# Ferrofluid_Display.net
KiCad netlist of a schematic drawn in Altium Designer
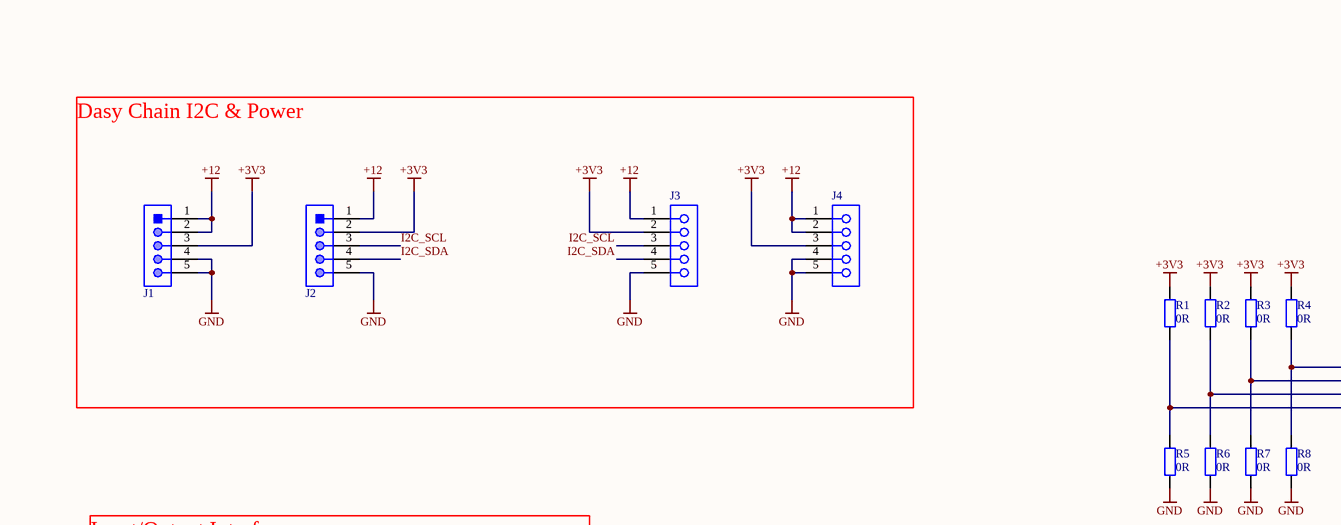
[diagram p0: Ferrofluid_Display.SchDoc, top left]
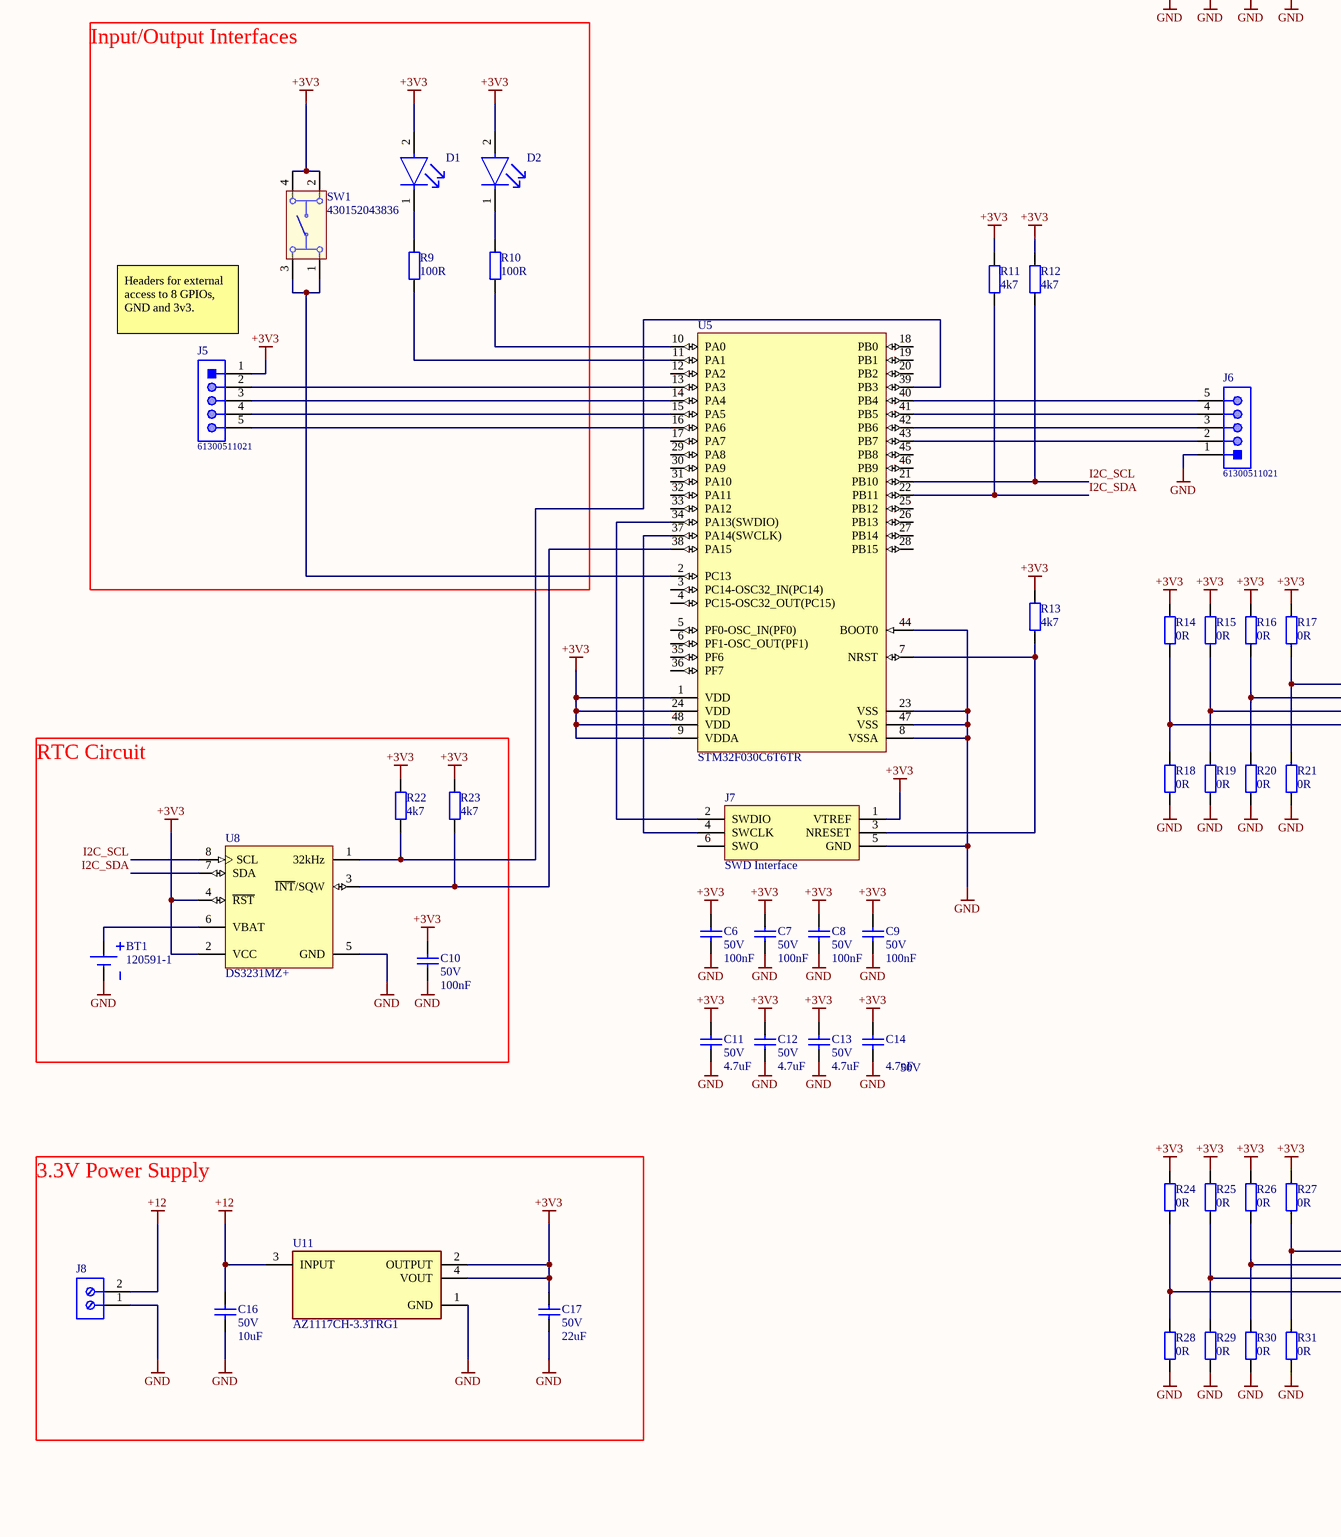
[diagram p1: Ferrofluid_Display.SchDoc, bottom left]
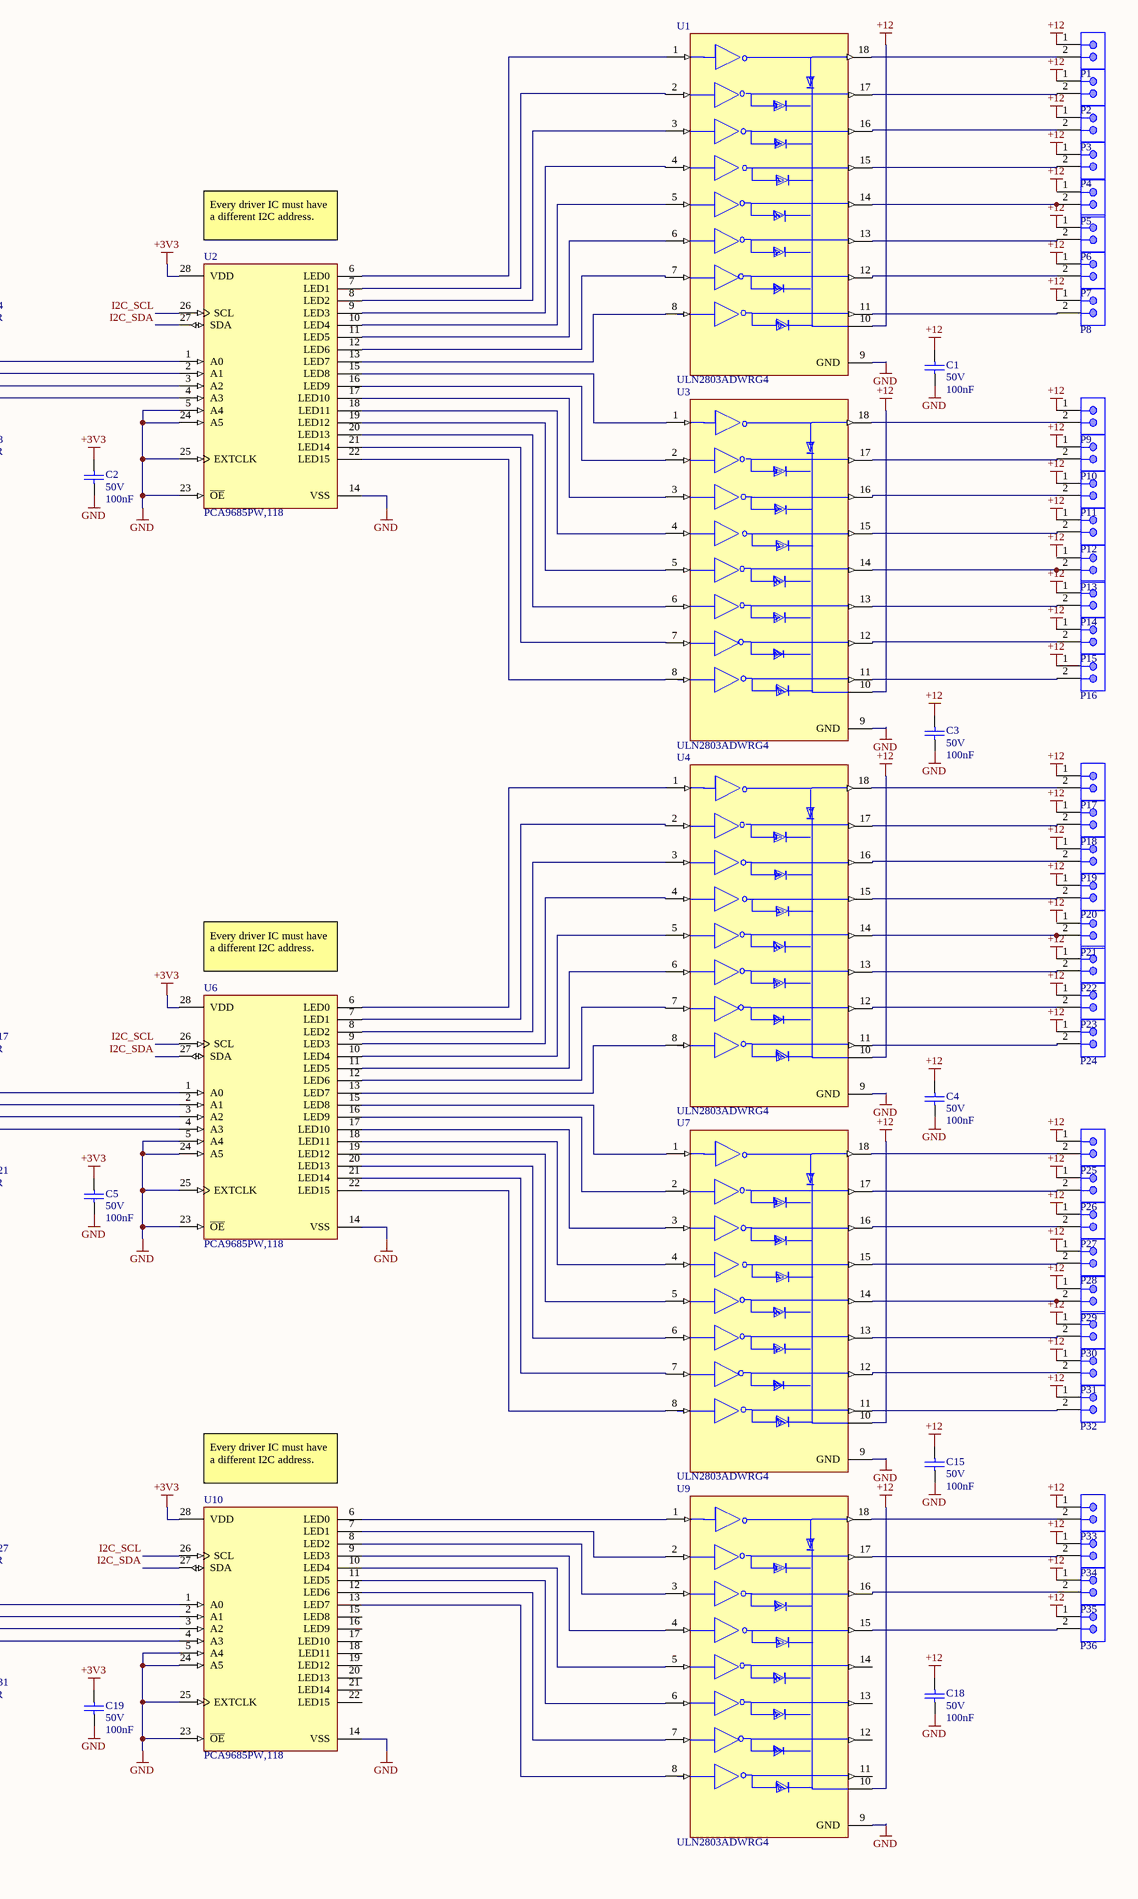
[diagram p2: Ferrofluid_Display.SchDoc, bottom right]

(export (version "E")
  (design (tool "Eeschema 10.0.6"))
  (components
    (comp (ref "BT1")
      (value "120591-1")
      (footprint "TECO-120591-1-2_V")
      (description "Lithium Battery Holder for CR2032 3V Cell")
      (fields (field (name "MANUFACTURER") "TE Connectivity"))
      (libsource (lib "Altium Content Vault") (part "TECO-120591-1-2"))
    )
    (comp (ref "C1")
      (value "100nF")
      (footprint "CAPC2013X88X50ML20T25")
      (description "Ceramic Capacitor X7R")
      (fields (field (name "VOLTAGE RATING") "50V") (field (name "Comment") "Cap_0805"))
      (libsource (lib "Ferrofluid_Display") (part "Cap_0805"))
    )
    (comp (ref "C2")
      (value "100nF")
      (footprint "CAPC2013X88X50ML20T25")
      (description "Ceramic Capacitor X7R")
      (fields (field (name "VOLTAGE RATING") "50V") (field (name "Comment") "Cap_0805"))
      (libsource (lib "Ferrofluid_Display") (part "Cap_0805"))
    )
    (comp (ref "C3")
      (value "100nF")
      (footprint "CAPC2013X88X50ML20T25")
      (description "Ceramic Capacitor X7R")
      (fields (field (name "VOLTAGE RATING") "50V") (field (name "Comment") "Cap_0805"))
      (libsource (lib "Ferrofluid_Display") (part "Cap_0805"))
    )
    (comp (ref "C4")
      (value "100nF")
      (footprint "CAPC2013X88X50ML20T25")
      (description "Ceramic Capacitor X7R")
      (fields (field (name "VOLTAGE RATING") "50V") (field (name "Comment") "Cap_0805"))
      (libsource (lib "Ferrofluid_Display") (part "Cap_0805"))
    )
    (comp (ref "C5")
      (value "100nF")
      (footprint "CAPC2013X88X50ML20T25")
      (description "Ceramic Capacitor X7R")
      (fields (field (name "VOLTAGE RATING") "50V") (field (name "Comment") "Cap_0805"))
      (libsource (lib "Ferrofluid_Display") (part "Cap_0805"))
    )
    (comp (ref "C6")
      (value "100nF")
      (footprint "CAPC2013X88X50ML20T25")
      (description "Ceramic Capacitor X7R")
      (fields (field (name "VOLTAGE RATING") "50V") (field (name "Comment") "Cap_0805"))
      (libsource (lib "Ferrofluid_Display") (part "Cap_0805"))
    )
    (comp (ref "C7")
      (value "100nF")
      (footprint "CAPC2013X88X50ML20T25")
      (description "Ceramic Capacitor X7R")
      (fields (field (name "VOLTAGE RATING") "50V") (field (name "Comment") "Cap_0805"))
      (libsource (lib "Ferrofluid_Display") (part "Cap_0805"))
    )
    (comp (ref "C8")
      (value "100nF")
      (footprint "CAPC2013X88X50ML20T25")
      (description "Ceramic Capacitor X7R")
      (fields (field (name "VOLTAGE RATING") "50V") (field (name "Comment") "Cap_0805"))
      (libsource (lib "Ferrofluid_Display") (part "Cap_0805"))
    )
    (comp (ref "C9")
      (value "100nF")
      (footprint "CAPC2013X88X50ML20T25")
      (description "Ceramic Capacitor X7R")
      (fields (field (name "VOLTAGE RATING") "50V") (field (name "Comment") "Cap_0805"))
      (libsource (lib "Ferrofluid_Display") (part "Cap_0805"))
    )
    (comp (ref "C10")
      (value "100nF")
      (footprint "CAPC2013X88X50ML20T25")
      (description "Ceramic Capacitor X7R")
      (fields (field (name "VOLTAGE RATING") "50V") (field (name "Comment") "Cap_0805"))
      (libsource (lib "Ferrofluid_Display") (part "Cap_0805"))
    )
    (comp (ref "C11")
      (value "4.7uF")
      (footprint "CAPC2013X88X50ML20T25")
      (description "Ceramic Capacitor X7R")
      (fields (field (name "VOLTAGE RATING") "50V") (field (name "Comment") "Cap_0805"))
      (libsource (lib "Ferrofluid_Display") (part "Cap_0805"))
    )
    (comp (ref "C12")
      (value "4.7uF")
      (footprint "CAPC2013X88X50ML20T25")
      (description "Ceramic Capacitor X7R")
      (fields (field (name "VOLTAGE RATING") "50V") (field (name "Comment") "Cap_0805"))
      (libsource (lib "Ferrofluid_Display") (part "Cap_0805"))
    )
    (comp (ref "C13")
      (value "4.7uF")
      (footprint "CAPC2013X88X50ML20T25")
      (description "Ceramic Capacitor X7R")
      (fields (field (name "VOLTAGE RATING") "50V") (field (name "Comment") "Cap_0805"))
      (libsource (lib "Ferrofluid_Display") (part "Cap_0805"))
    )
    (comp (ref "C14")
      (value "4.7uF")
      (footprint "CAPC2013X88X50ML20T25")
      (description "Ceramic Capacitor X7R")
      (fields (field (name "VOLTAGE RATING") "50V") (field (name "Comment") "Cap_0805"))
      (libsource (lib "Ferrofluid_Display") (part "Cap_0805"))
    )
    (comp (ref "C15")
      (value "100nF")
      (footprint "CAPC2013X88X50ML20T25")
      (description "Ceramic Capacitor X7R")
      (fields (field (name "VOLTAGE RATING") "50V") (field (name "Comment") "Cap_0805"))
      (libsource (lib "Ferrofluid_Display") (part "Cap_0805"))
    )
    (comp (ref "C16")
      (value "10uF")
      (footprint "CAPC2013X88X50ML20T25")
      (description "Ceramic Capacitor X7R")
      (fields (field (name "VOLTAGE RATING") "50V") (field (name "Comment") "Cap_0805"))
      (libsource (lib "Ferrofluid_Display") (part "Cap_0805"))
    )
    (comp (ref "C17")
      (value "22uF")
      (footprint "CAPC2013X88X50ML20T25")
      (description "Ceramic Capacitor X7R")
      (fields (field (name "VOLTAGE RATING") "50V") (field (name "Comment") "Cap_0805"))
      (libsource (lib "Ferrofluid_Display") (part "Cap_0805"))
    )
    (comp (ref "C18")
      (value "100nF")
      (footprint "CAPC2013X88X50ML20T25")
      (description "Ceramic Capacitor X7R")
      (fields (field (name "VOLTAGE RATING") "50V") (field (name "Comment") "Cap_0805"))
      (libsource (lib "Ferrofluid_Display") (part "Cap_0805"))
    )
    (comp (ref "C19")
      (value "100nF")
      (footprint "CAPC2013X88X50ML20T25")
      (description "Ceramic Capacitor X7R")
      (fields (field (name "VOLTAGE RATING") "50V") (field (name "Comment") "Cap_0805"))
      (libsource (lib "Ferrofluid_Display") (part "Cap_0805"))
    )
    (comp (ref "D1")
      (value "LTST-C150AKT")
      (footprint "FP-LTST-C150AKT-MFG")
      (description "LED AMBER CLEAR SMD")
      (fields
        (field (name "MANUFACTURER") "Lite-On")
        (field (name "OCTOPART") "https://octopart.com/ltst-c150akt-lite-on-549804")
      )
      (libsource (lib "Altium Content Vault") (part "8706943c75ba83719d021d2fdc84c58"))
    )
    (comp (ref "D2")
      (value "LTST-C150AKT")
      (footprint "FP-LTST-C150AKT-MFG")
      (description "LED AMBER CLEAR SMD")
      (fields
        (field (name "MANUFACTURER") "Lite-On")
        (field (name "OCTOPART") "https://octopart.com/ltst-c150akt-lite-on-549804")
      )
      (libsource (lib "Altium Content Vault") (part "8706943c75ba83719d021d2fdc84c58"))
    )
    (comp (ref "J1")
      (value "61300511021")
      (footprint "61300511021")
      (description "THT Angled Pin Header WR-PHD, Pitch 2.54 mm, Single Row, 5 pins")
      (fields (field (name "MANUFACTURER") "Wurth Elektronik") (field (name "PUBLISHER") "WurthElektronik"))
      (libsource (lib "Altium Content Vault") (part "WE-CN-1P-M-R5"))
    )
    (comp (ref "J2")
      (value "61300511021")
      (footprint "61300511021")
      (description "THT Angled Pin Header WR-PHD, Pitch 2.54 mm, Single Row, 5 pins")
      (fields (field (name "MANUFACTURER") "Wurth Elektronik") (field (name "PUBLISHER") "WurthElektronik"))
      (libsource (lib "Altium Content Vault") (part "WE-CN-1P-M-R5"))
    )
    (comp (ref "J3")
      (value "SSQ-105-02-T-S-RA")
      (footprint "SMTC-SSQ-105-02-X-S-RA")
      (description "SQ Post Socket, Through-hole, Right Angle, -55 to 105 degC, 2.54 mm Pitch, 5-Pin, Female, RoHS")
      (fields (field (name "MANUFACTURER") "Samtec"))
      (libsource (lib "Altium Content Vault") (part "SMTC-SSQ-105-02-X-S-RA"))
    )
    (comp (ref "J4")
      (value "SSQ-105-02-T-S-RA")
      (footprint "SMTC-SSQ-105-02-X-S-RA")
      (description "SQ Post Socket, Through-hole, Right Angle, -55 to 105 degC, 2.54 mm Pitch, 5-Pin, Female, RoHS")
      (fields (field (name "MANUFACTURER") "Samtec"))
      (libsource (lib "Altium Content Vault") (part "SMTC-SSQ-105-02-X-S-RA"))
    )
    (comp (ref "J5")
      (value "61300511021")
      (footprint "61300511021")
      (description "THT Angled Pin Header WR-PHD, Pitch 2.54 mm, Single Row, 5 pins")
      (fields (field (name "MANUFACTURER") "Wurth Elektronik") (field (name "PUBLISHER") "WurthElektronik"))
      (libsource (lib "Altium Content Vault") (part "WE-CN-1P-M-R5"))
    )
    (comp (ref "J6")
      (value "61300511021")
      (footprint "61300511021")
      (description "THT Angled Pin Header WR-PHD, Pitch 2.54 mm, Single Row, 5 pins")
      (fields (field (name "MANUFACTURER") "Wurth Elektronik") (field (name "PUBLISHER") "WurthElektronik"))
      (libsource (lib "") (part "WE-CN-1P-M-R5_1"))
    )
    (comp (ref "J7")
      (value "SWD Interface")
      (footprint "J-Link_6-pin_Needle_Adapter")
      (description "J-Link 6-pin Needle Adapter")
      (libsource (lib "Ferrofluid_Display") (part "J-Link_6-pin_Needle_Adapter"))
    )
    (comp (ref "J8")
      (value "691102710002")
      (footprint "691102710002")
      (description "Series 102 - 5.00 mm Horizontal Entry Modular with Pressure Clamp WR-TBL, 2 pin")
      (fields (field (name "MANUFACTURER") "Wurth Elektronik") (field (name "PUBLISHER") "WurthElektronik"))
      (libsource (lib "Altium Content Vault") (part "WE-CN-1P-F-TB2"))
    )
    (comp (ref "P1")
      (value "5-146280-2")
      (footprint "ELECTROMAGNET")
      (fields (field (name "MANUFACTURER") "TE Connectivity"))
      (libsource (lib "Ferrofluid_Display") (part "Magnet"))
    )
    (comp (ref "P2")
      (value "5-146280-2")
      (footprint "ELECTROMAGNET")
      (fields (field (name "MANUFACTURER") "TE Connectivity"))
      (libsource (lib "Ferrofluid_Display") (part "Magnet"))
    )
    (comp (ref "P3")
      (value "5-146280-2")
      (footprint "ELECTROMAGNET")
      (fields (field (name "MANUFACTURER") "TE Connectivity"))
      (libsource (lib "Ferrofluid_Display") (part "Magnet"))
    )
    (comp (ref "P4")
      (value "5-146280-2")
      (footprint "ELECTROMAGNET")
      (fields (field (name "MANUFACTURER") "TE Connectivity"))
      (libsource (lib "Ferrofluid_Display") (part "Magnet"))
    )
    (comp (ref "P5")
      (value "5-146280-2")
      (footprint "ELECTROMAGNET")
      (fields (field (name "MANUFACTURER") "TE Connectivity"))
      (libsource (lib "Ferrofluid_Display") (part "Magnet"))
    )
    (comp (ref "P6")
      (value "5-146280-2")
      (footprint "ELECTROMAGNET")
      (fields (field (name "MANUFACTURER") "TE Connectivity"))
      (libsource (lib "Ferrofluid_Display") (part "Magnet"))
    )
    (comp (ref "P7")
      (value "5-146280-2")
      (footprint "ELECTROMAGNET")
      (fields (field (name "MANUFACTURER") "TE Connectivity"))
      (libsource (lib "Ferrofluid_Display") (part "Magnet"))
    )
    (comp (ref "P8")
      (value "5-146280-2")
      (footprint "ELECTROMAGNET")
      (fields (field (name "MANUFACTURER") "TE Connectivity"))
      (libsource (lib "Ferrofluid_Display") (part "Magnet"))
    )
    (comp (ref "P9")
      (value "5-146280-2")
      (footprint "ELECTROMAGNET")
      (fields (field (name "MANUFACTURER") "TE Connectivity"))
      (libsource (lib "Ferrofluid_Display") (part "Magnet"))
    )
    (comp (ref "P10")
      (value "5-146280-2")
      (footprint "ELECTROMAGNET")
      (fields (field (name "MANUFACTURER") "TE Connectivity"))
      (libsource (lib "Ferrofluid_Display") (part "Magnet"))
    )
    (comp (ref "P11")
      (value "5-146280-2")
      (footprint "ELECTROMAGNET")
      (fields (field (name "MANUFACTURER") "TE Connectivity"))
      (libsource (lib "Ferrofluid_Display") (part "Magnet"))
    )
    (comp (ref "P12")
      (value "5-146280-2")
      (footprint "ELECTROMAGNET")
      (fields (field (name "MANUFACTURER") "TE Connectivity"))
      (libsource (lib "Ferrofluid_Display") (part "Magnet"))
    )
    (comp (ref "P13")
      (value "5-146280-2")
      (footprint "ELECTROMAGNET")
      (fields (field (name "MANUFACTURER") "TE Connectivity"))
      (libsource (lib "Ferrofluid_Display") (part "Magnet"))
    )
    (comp (ref "P14")
      (value "5-146280-2")
      (footprint "ELECTROMAGNET")
      (fields (field (name "MANUFACTURER") "TE Connectivity"))
      (libsource (lib "Ferrofluid_Display") (part "Magnet"))
    )
    (comp (ref "P15")
      (value "5-146280-2")
      (footprint "ELECTROMAGNET")
      (fields (field (name "MANUFACTURER") "TE Connectivity"))
      (libsource (lib "Ferrofluid_Display") (part "Magnet"))
    )
    (comp (ref "P16")
      (value "5-146280-2")
      (footprint "ELECTROMAGNET")
      (fields (field (name "MANUFACTURER") "TE Connectivity"))
      (libsource (lib "Ferrofluid_Display") (part "Magnet"))
    )
    (comp (ref "P17")
      (value "5-146280-2")
      (footprint "ELECTROMAGNET")
      (fields (field (name "MANUFACTURER") "TE Connectivity"))
      (libsource (lib "Ferrofluid_Display") (part "Magnet"))
    )
    (comp (ref "P18")
      (value "5-146280-2")
      (footprint "ELECTROMAGNET")
      (fields (field (name "MANUFACTURER") "TE Connectivity"))
      (libsource (lib "Ferrofluid_Display") (part "Magnet"))
    )
    (comp (ref "P19")
      (value "5-146280-2")
      (footprint "ELECTROMAGNET")
      (fields (field (name "MANUFACTURER") "TE Connectivity"))
      (libsource (lib "Ferrofluid_Display") (part "Magnet"))
    )
    (comp (ref "P20")
      (value "5-146280-2")
      (footprint "ELECTROMAGNET")
      (fields (field (name "MANUFACTURER") "TE Connectivity"))
      (libsource (lib "Ferrofluid_Display") (part "Magnet"))
    )
    (comp (ref "P21")
      (value "5-146280-2")
      (footprint "ELECTROMAGNET")
      (fields (field (name "MANUFACTURER") "TE Connectivity"))
      (libsource (lib "Ferrofluid_Display") (part "Magnet"))
    )
    (comp (ref "P22")
      (value "5-146280-2")
      (footprint "ELECTROMAGNET")
      (fields (field (name "MANUFACTURER") "TE Connectivity"))
      (libsource (lib "Ferrofluid_Display") (part "Magnet"))
    )
    (comp (ref "P23")
      (value "5-146280-2")
      (footprint "ELECTROMAGNET")
      (fields (field (name "MANUFACTURER") "TE Connectivity"))
      (libsource (lib "Ferrofluid_Display") (part "Magnet"))
    )
    (comp (ref "P24")
      (value "5-146280-2")
      (footprint "ELECTROMAGNET")
      (fields (field (name "MANUFACTURER") "TE Connectivity"))
      (libsource (lib "Ferrofluid_Display") (part "Magnet"))
    )
    (comp (ref "P25")
      (value "5-146280-2")
      (footprint "ELECTROMAGNET")
      (fields (field (name "MANUFACTURER") "TE Connectivity"))
      (libsource (lib "Ferrofluid_Display") (part "Magnet"))
    )
    (comp (ref "P26")
      (value "5-146280-2")
      (footprint "ELECTROMAGNET")
      (fields (field (name "MANUFACTURER") "TE Connectivity"))
      (libsource (lib "Ferrofluid_Display") (part "Magnet"))
    )
    (comp (ref "P27")
      (value "5-146280-2")
      (footprint "ELECTROMAGNET")
      (fields (field (name "MANUFACTURER") "TE Connectivity"))
      (libsource (lib "Ferrofluid_Display") (part "Magnet"))
    )
    (comp (ref "P28")
      (value "5-146280-2")
      (footprint "ELECTROMAGNET")
      (fields (field (name "MANUFACTURER") "TE Connectivity"))
      (libsource (lib "Ferrofluid_Display") (part "Magnet"))
    )
    (comp (ref "P29")
      (value "5-146280-2")
      (footprint "ELECTROMAGNET")
      (fields (field (name "MANUFACTURER") "TE Connectivity"))
      (libsource (lib "Ferrofluid_Display") (part "Magnet"))
    )
    (comp (ref "P30")
      (value "5-146280-2")
      (footprint "ELECTROMAGNET")
      (fields (field (name "MANUFACTURER") "TE Connectivity"))
      (libsource (lib "Ferrofluid_Display") (part "Magnet"))
    )
    (comp (ref "P31")
      (value "5-146280-2")
      (footprint "ELECTROMAGNET")
      (fields (field (name "MANUFACTURER") "TE Connectivity"))
      (libsource (lib "Ferrofluid_Display") (part "Magnet"))
    )
    (comp (ref "P32")
      (value "5-146280-2")
      (footprint "ELECTROMAGNET")
      (fields (field (name "MANUFACTURER") "TE Connectivity"))
      (libsource (lib "Ferrofluid_Display") (part "Magnet"))
    )
    (comp (ref "P33")
      (value "5-146280-2")
      (footprint "ELECTROMAGNET")
      (fields (field (name "MANUFACTURER") "TE Connectivity"))
      (libsource (lib "Ferrofluid_Display") (part "Magnet"))
    )
    (comp (ref "P34")
      (value "5-146280-2")
      (footprint "ELECTROMAGNET")
      (fields (field (name "MANUFACTURER") "TE Connectivity"))
      (libsource (lib "Ferrofluid_Display") (part "Magnet"))
    )
    (comp (ref "P35")
      (value "5-146280-2")
      (footprint "ELECTROMAGNET")
      (fields (field (name "MANUFACTURER") "TE Connectivity"))
      (libsource (lib "Ferrofluid_Display") (part "Magnet"))
    )
    (comp (ref "P36")
      (value "5-146280-2")
      (footprint "ELECTROMAGNET")
      (fields (field (name "MANUFACTURER") "TE Connectivity"))
      (libsource (lib "Ferrofluid_Display") (part "Magnet"))
    )
    (comp (ref "R1")
      (value "0R")
      (footprint "RESC2013X50X30ML20T20")
      (description "Resistor")
      (fields (field (name "TOLERANCE") "1%") (field (name "Comment") "Res_0805"))
      (libsource (lib "Ferrofluid_Display") (part "Res_0805"))
    )
    (comp (ref "R2")
      (value "0R")
      (footprint "RESC2013X50X30ML20T20")
      (description "Resistor")
      (fields (field (name "TOLERANCE") "1%") (field (name "Comment") "Res_0805"))
      (libsource (lib "Ferrofluid_Display") (part "Res_0805"))
    )
    (comp (ref "R3")
      (value "0R")
      (footprint "RESC2013X50X30ML20T20")
      (description "Resistor")
      (fields (field (name "TOLERANCE") "1%") (field (name "Comment") "Res_0805"))
      (libsource (lib "Ferrofluid_Display") (part "Res_0805"))
    )
    (comp (ref "R4")
      (value "0R")
      (footprint "RESC2013X50X30ML20T20")
      (description "Resistor")
      (fields (field (name "TOLERANCE") "1%") (field (name "Comment") "Res_0805"))
      (libsource (lib "Ferrofluid_Display") (part "Res_0805"))
    )
    (comp (ref "R5")
      (value "0R")
      (footprint "RESC2013X50X30ML20T20")
      (description "Resistor")
      (fields (field (name "TOLERANCE") "1%") (field (name "Comment") "Res_0805"))
      (libsource (lib "Ferrofluid_Display") (part "Res_0805"))
    )
    (comp (ref "R6")
      (value "0R")
      (footprint "RESC2013X50X30ML20T20")
      (description "Resistor")
      (fields (field (name "TOLERANCE") "1%") (field (name "Comment") "Res_0805"))
      (libsource (lib "Ferrofluid_Display") (part "Res_0805"))
    )
    (comp (ref "R7")
      (value "0R")
      (footprint "RESC2013X50X30ML20T20")
      (description "Resistor")
      (fields (field (name "TOLERANCE") "1%") (field (name "Comment") "Res_0805"))
      (libsource (lib "Ferrofluid_Display") (part "Res_0805"))
    )
    (comp (ref "R8")
      (value "0R")
      (footprint "RESC2013X50X30ML20T20")
      (description "Resistor")
      (fields (field (name "TOLERANCE") "1%") (field (name "Comment") "Res_0805"))
      (libsource (lib "Ferrofluid_Display") (part "Res_0805"))
    )
    (comp (ref "R9")
      (value "100R")
      (footprint "RESC2013X50X30ML20T20")
      (description "Resistor")
      (fields (field (name "TOLERANCE") "1%") (field (name "Comment") "Res_0805"))
      (libsource (lib "Ferrofluid_Display") (part "Res_0805"))
    )
    (comp (ref "R10")
      (value "100R")
      (footprint "RESC2013X50X30ML20T20")
      (description "Resistor")
      (fields (field (name "TOLERANCE") "1%") (field (name "Comment") "Res_0805"))
      (libsource (lib "Ferrofluid_Display") (part "Res_0805"))
    )
    (comp (ref "R11")
      (value "4k7")
      (footprint "RESC2013X50X30ML20T20")
      (description "Resistor")
      (fields (field (name "TOLERANCE") "1%") (field (name "Comment") "Res_0805"))
      (libsource (lib "Ferrofluid_Display") (part "Res_0805"))
    )
    (comp (ref "R12")
      (value "4k7")
      (footprint "RESC2013X50X30ML20T20")
      (description "Resistor")
      (fields (field (name "TOLERANCE") "1%") (field (name "Comment") "Res_0805"))
      (libsource (lib "Ferrofluid_Display") (part "Res_0805"))
    )
    (comp (ref "R13")
      (value "4k7")
      (footprint "RESC2013X50X30ML20T20")
      (description "Resistor")
      (fields (field (name "TOLERANCE") "1%") (field (name "Comment") "Res_0805"))
      (libsource (lib "Ferrofluid_Display") (part "Res_0805"))
    )
    (comp (ref "R14")
      (value "0R")
      (footprint "RESC2013X50X30ML20T20")
      (description "Resistor")
      (fields (field (name "TOLERANCE") "1%") (field (name "Comment") "Res_0805"))
      (libsource (lib "Ferrofluid_Display") (part "Res_0805"))
    )
    (comp (ref "R15")
      (value "0R")
      (footprint "RESC2013X50X30ML20T20")
      (description "Resistor")
      (fields (field (name "TOLERANCE") "1%") (field (name "Comment") "Res_0805"))
      (libsource (lib "Ferrofluid_Display") (part "Res_0805"))
    )
    (comp (ref "R16")
      (value "0R")
      (footprint "RESC2013X50X30ML20T20")
      (description "Resistor")
      (fields (field (name "TOLERANCE") "1%") (field (name "Comment") "Res_0805"))
      (libsource (lib "Ferrofluid_Display") (part "Res_0805"))
    )
    (comp (ref "R17")
      (value "0R")
      (footprint "RESC2013X50X30ML20T20")
      (description "Resistor")
      (fields (field (name "TOLERANCE") "1%") (field (name "Comment") "Res_0805"))
      (libsource (lib "Ferrofluid_Display") (part "Res_0805"))
    )
    (comp (ref "R18")
      (value "0R")
      (footprint "RESC2013X50X30ML20T20")
      (description "Resistor")
      (fields (field (name "TOLERANCE") "1%") (field (name "Comment") "Res_0805"))
      (libsource (lib "Ferrofluid_Display") (part "Res_0805"))
    )
    (comp (ref "R19")
      (value "0R")
      (footprint "RESC2013X50X30ML20T20")
      (description "Resistor")
      (fields (field (name "TOLERANCE") "1%") (field (name "Comment") "Res_0805"))
      (libsource (lib "Ferrofluid_Display") (part "Res_0805"))
    )
    (comp (ref "R20")
      (value "0R")
      (footprint "RESC2013X50X30ML20T20")
      (description "Resistor")
      (fields (field (name "TOLERANCE") "1%") (field (name "Comment") "Res_0805"))
      (libsource (lib "Ferrofluid_Display") (part "Res_0805"))
    )
    (comp (ref "R21")
      (value "0R")
      (footprint "RESC2013X50X30ML20T20")
      (description "Resistor")
      (fields (field (name "TOLERANCE") "1%") (field (name "Comment") "Res_0805"))
      (libsource (lib "Ferrofluid_Display") (part "Res_0805"))
    )
    (comp (ref "R22")
      (value "4k7")
      (footprint "RESC2013X50X30ML20T20")
      (description "Resistor")
      (fields (field (name "TOLERANCE") "1%") (field (name "Comment") "Res_0805"))
      (libsource (lib "Ferrofluid_Display") (part "Res_0805"))
    )
    (comp (ref "R23")
      (value "4k7")
      (footprint "RESC2013X50X30ML20T20")
      (description "Resistor")
      (fields (field (name "TOLERANCE") "1%") (field (name "Comment") "Res_0805"))
      (libsource (lib "Ferrofluid_Display") (part "Res_0805"))
    )
    (comp (ref "R24")
      (value "0R")
      (footprint "RESC2013X50X30ML20T20")
      (description "Resistor")
      (fields (field (name "TOLERANCE") "1%") (field (name "Comment") "Res_0805"))
      (libsource (lib "Ferrofluid_Display") (part "Res_0805"))
    )
    (comp (ref "R25")
      (value "0R")
      (footprint "RESC2013X50X30ML20T20")
      (description "Resistor")
      (fields (field (name "TOLERANCE") "1%") (field (name "Comment") "Res_0805"))
      (libsource (lib "Ferrofluid_Display") (part "Res_0805"))
    )
    (comp (ref "R26")
      (value "0R")
      (footprint "RESC2013X50X30ML20T20")
      (description "Resistor")
      (fields (field (name "TOLERANCE") "1%") (field (name "Comment") "Res_0805"))
      (libsource (lib "Ferrofluid_Display") (part "Res_0805"))
    )
    (comp (ref "R27")
      (value "0R")
      (footprint "RESC2013X50X30ML20T20")
      (description "Resistor")
      (fields (field (name "TOLERANCE") "1%") (field (name "Comment") "Res_0805"))
      (libsource (lib "Ferrofluid_Display") (part "Res_0805"))
    )
    (comp (ref "R28")
      (value "0R")
      (footprint "RESC2013X50X30ML20T20")
      (description "Resistor")
      (fields (field (name "TOLERANCE") "1%") (field (name "Comment") "Res_0805"))
      (libsource (lib "Ferrofluid_Display") (part "Res_0805"))
    )
    (comp (ref "R29")
      (value "0R")
      (footprint "RESC2013X50X30ML20T20")
      (description "Resistor")
      (fields (field (name "TOLERANCE") "1%") (field (name "Comment") "Res_0805"))
      (libsource (lib "Ferrofluid_Display") (part "Res_0805"))
    )
    (comp (ref "R30")
      (value "0R")
      (footprint "RESC2013X50X30ML20T20")
      (description "Resistor")
      (fields (field (name "TOLERANCE") "1%") (field (name "Comment") "Res_0805"))
      (libsource (lib "Ferrofluid_Display") (part "Res_0805"))
    )
    (comp (ref "R31")
      (value "0R")
      (footprint "RESC2013X50X30ML20T20")
      (description "Resistor")
      (fields (field (name "TOLERANCE") "1%") (field (name "Comment") "Res_0805"))
      (libsource (lib "Ferrofluid_Display") (part "Res_0805"))
    )
    (comp (ref "SW1")
      (value "430152043836")
      (footprint "430152043836")
      (description "WS-TASV SMD Tact Switch 6X6 mm")
      (fields (field (name "MANUFACTURER") "Wuerth Elektronik"))
      (libsource (lib "Altium Content Vault") (part "WE-TACT-SW-4"))
    )
    (comp (ref "U1")
      (value "ULN2803ADWRG4")
      (footprint "FP-DW0018A-MFG")
      (description "TRANS 8NPN DARL 50V 0.5A 18SO")
      (fields
        (field (name "MANUFACTURER") "Texas Instruments")
        (field (name "OCTOPART") "https://octopart.com/uln2803adwrg4-texas+instruments-2343640")
      )
      (libsource (lib "Altium Content Vault") (part "9cac77ed03a2a3c2ed33a396e3d2829"))
    )
    (comp (ref "U2")
      (value "PCA9685PW,118")
      (footprint "FP-SOT361-1-MFG")
      (description "IC LED DRIVER RGBA 28-TSSOP")
      (fields
        (field (name "MANUFACTURER") "NXP Semiconductors")
        (field (name "OCTOPART") "https://octopart.com/pca9685pw%2C118-nxp+semiconductors-11853435")
      )
      (libsource (lib "Altium Content Vault") (part "50b6f6febb80a1ca83d1eae7256368c"))
    )
    (comp (ref "U3")
      (value "ULN2803ADWRG4")
      (footprint "FP-DW0018A-MFG")
      (description "TRANS 8NPN DARL 50V 0.5A 18SO")
      (fields
        (field (name "MANUFACTURER") "Texas Instruments")
        (field (name "OCTOPART") "https://octopart.com/uln2803adwrg4-texas+instruments-2343640")
      )
      (libsource (lib "Altium Content Vault") (part "9cac77ed03a2a3c2ed33a396e3d2829"))
    )
    (comp (ref "U4")
      (value "ULN2803ADWRG4")
      (footprint "FP-DW0018A-MFG")
      (description "TRANS 8NPN DARL 50V 0.5A 18SO")
      (fields
        (field (name "MANUFACTURER") "Texas Instruments")
        (field (name "OCTOPART") "https://octopart.com/uln2803adwrg4-texas+instruments-2343640")
      )
      (libsource (lib "Altium Content Vault") (part "9cac77ed03a2a3c2ed33a396e3d2829"))
    )
    (comp (ref "U5")
      (value "STM32F030C6T6TR")
      (footprint "STM-LQFP48_M")
      (fields (field (name "MANUFACTURER") "STMicroelectronics"))
      (libsource (lib "Altium Content Vault") (part "STM-STM32F030C6-LQFP48_A"))
    )
    (comp (ref "U6")
      (value "PCA9685PW,118")
      (footprint "FP-SOT361-1-MFG")
      (description "IC LED DRIVER RGBA 28-TSSOP")
      (fields
        (field (name "MANUFACTURER") "NXP Semiconductors")
        (field (name "OCTOPART") "https://octopart.com/pca9685pw%2C118-nxp+semiconductors-11853435")
      )
      (libsource (lib "Altium Content Vault") (part "50b6f6febb80a1ca83d1eae7256368c"))
    )
    (comp (ref "U7")
      (value "ULN2803ADWRG4")
      (footprint "FP-DW0018A-MFG")
      (description "TRANS 8NPN DARL 50V 0.5A 18SO")
      (fields
        (field (name "MANUFACTURER") "Texas Instruments")
        (field (name "OCTOPART") "https://octopart.com/uln2803adwrg4-texas+instruments-2343640")
      )
      (libsource (lib "Altium Content Vault") (part "9cac77ed03a2a3c2ed33a396e3d2829"))
    )
    (comp (ref "U8")
      (value "DS3231MZ+")
      (footprint "S8MK+1_N")
      (description "+/-5ppm, MEMS based Real-Time Clock, I2C Interface, 8-Pin SO, -40 to 85 degC, Pb-Free")
      (libsource (lib "Altium Content Vault") (part "PR-RTC-DS3231M-IL8"))
    )
    (comp (ref "U9")
      (value "ULN2803ADWRG4")
      (footprint "FP-DW0018A-MFG")
      (description "TRANS 8NPN DARL 50V 0.5A 18SO")
      (fields
        (field (name "MANUFACTURER") "Texas Instruments")
        (field (name "OCTOPART") "https://octopart.com/uln2803adwrg4-texas+instruments-2343640")
      )
      (libsource (lib "Altium Content Vault") (part "9cac77ed03a2a3c2ed33a396e3d2829"))
    )
    (comp (ref "U10")
      (value "PCA9685PW,118")
      (footprint "FP-SOT361-1-MFG")
      (description "IC LED DRIVER RGBA 28-TSSOP")
      (fields
        (field (name "MANUFACTURER") "NXP Semiconductors")
        (field (name "OCTOPART") "https://octopart.com/pca9685pw%2C118-nxp+semiconductors-11853435")
      )
      (libsource (lib "Altium Content Vault") (part "50b6f6febb80a1ca83d1eae7256368c"))
    )
    (comp (ref "U11")
      (value "AZ1117CH-3.3TRG1")
      (footprint "FP-SOT223-MFG")
      (description "IC REG LINEAR 3.3V 800MA SOT223")
      (libsource (lib "Altium Content Vault") (part "bae10108a039f7d2bfd31a2f0f6c252"))
    )
  )
  (nets
    (net (code "1") (name "+3V3") (class "Default")
      (node (ref "C10") (pin "2") (pinfunction "2_2") (pintype "passive"))
      (node (ref "C11") (pin "2") (pinfunction "2_2") (pintype "passive"))
      (node (ref "C12") (pin "2") (pinfunction "2_2") (pintype "passive"))
      (node (ref "C13") (pin "2") (pinfunction "2_2") (pintype "passive"))
      (node (ref "C14") (pin "2") (pinfunction "2_2") (pintype "passive"))
      (node (ref "C17") (pin "2") (pinfunction "2_2") (pintype "passive"))
      (node (ref "C19") (pin "2") (pinfunction "2_2") (pintype "passive"))
      (node (ref "C2") (pin "2") (pinfunction "2_2") (pintype "passive"))
      (node (ref "C5") (pin "2") (pinfunction "2_2") (pintype "passive"))
      (node (ref "C6") (pin "2") (pinfunction "2_2") (pintype "passive"))
      (node (ref "C7") (pin "2") (pinfunction "2_2") (pintype "passive"))
      (node (ref "C8") (pin "2") (pinfunction "2_2") (pintype "passive"))
      (node (ref "C9") (pin "2") (pinfunction "2_2") (pintype "passive"))
      (node (ref "D1") (pin "2") (pinfunction "A_2") (pintype "passive"))
      (node (ref "D2") (pin "2") (pinfunction "A_2") (pintype "passive"))
      (node (ref "J1") (pin "3") (pinfunction "3_3") (pintype "passive"))
      (node (ref "J2") (pin "2") (pinfunction "2_2") (pintype "passive"))
      (node (ref "J3") (pin "2") (pinfunction "2_2") (pintype "passive"))
      (node (ref "J4") (pin "3") (pinfunction "3_3") (pintype "passive"))
      (node (ref "J5") (pin "1") (pinfunction "1_1") (pintype "passive"))
      (node (ref "J7") (pin "1") (pinfunction "VTREF_1") (pintype "passive"))
      (node (ref "R1") (pin "2") (pinfunction "2_2") (pintype "passive"))
      (node (ref "R11") (pin "2") (pinfunction "2_2") (pintype "passive"))
      (node (ref "R12") (pin "2") (pinfunction "2_2") (pintype "passive"))
      (node (ref "R13") (pin "2") (pinfunction "2_2") (pintype "passive"))
      (node (ref "R14") (pin "2") (pinfunction "2_2") (pintype "passive"))
      (node (ref "R15") (pin "2") (pinfunction "2_2") (pintype "passive"))
      (node (ref "R16") (pin "2") (pinfunction "2_2") (pintype "passive"))
      (node (ref "R17") (pin "2") (pinfunction "2_2") (pintype "passive"))
      (node (ref "R2") (pin "2") (pinfunction "2_2") (pintype "passive"))
      (node (ref "R22") (pin "2") (pinfunction "2_2") (pintype "passive"))
      (node (ref "R23") (pin "2") (pinfunction "2_2") (pintype "passive"))
      (node (ref "R24") (pin "2") (pinfunction "2_2") (pintype "passive"))
      (node (ref "R25") (pin "2") (pinfunction "2_2") (pintype "passive"))
      (node (ref "R26") (pin "2") (pinfunction "2_2") (pintype "passive"))
      (node (ref "R27") (pin "2") (pinfunction "2_2") (pintype "passive"))
      (node (ref "R3") (pin "2") (pinfunction "2_2") (pintype "passive"))
      (node (ref "R4") (pin "2") (pinfunction "2_2") (pintype "passive"))
      (node (ref "SW1") (pin "2") (pinfunction "2_2") (pintype "passive"))
      (node (ref "SW1") (pin "4") (pinfunction "4_4") (pintype "passive"))
      (node (ref "U10") (pin "28") (pinfunction "VDD_28") (pintype "power_in"))
      (node (ref "U11") (pin "2") (pinfunction "OUTPUT_2") (pintype "power_in"))
      (node (ref "U11") (pin "4") (pinfunction "VOUT_4") (pintype "power_in"))
      (node (ref "U2") (pin "28") (pinfunction "VDD_28") (pintype "power_in"))
      (node (ref "U5") (pin "1") (pinfunction "VDD_1") (pintype "power_in"))
      (node (ref "U5") (pin "24") (pinfunction "VDD_24") (pintype "power_in"))
      (node (ref "U5") (pin "48") (pinfunction "VDD_48") (pintype "power_in"))
      (node (ref "U5") (pin "9") (pinfunction "VDDA_9") (pintype "power_in"))
      (node (ref "U6") (pin "28") (pinfunction "VDD_28") (pintype "power_in"))
      (node (ref "U8") (pin "2") (pinfunction "VCC_2") (pintype "power_in"))
      (node (ref "U8") (pin "4") (pinfunction "~{RST}_4") (pintype "bidirectional"))
    )
    (net (code "2") (name "+12") (class "Default")
      (node (ref "C1") (pin "2") (pinfunction "2_2") (pintype "passive"))
      (node (ref "C15") (pin "2") (pinfunction "2_2") (pintype "passive"))
      (node (ref "C16") (pin "2") (pinfunction "2_2") (pintype "passive"))
      (node (ref "C18") (pin "2") (pinfunction "2_2") (pintype "passive"))
      (node (ref "C3") (pin "2") (pinfunction "2_2") (pintype "passive"))
      (node (ref "C4") (pin "2") (pinfunction "2_2") (pintype "passive"))
      (node (ref "J1") (pin "1") (pinfunction "1_1") (pintype "passive"))
      (node (ref "J1") (pin "2") (pinfunction "2_2") (pintype "passive"))
      (node (ref "J2") (pin "1") (pinfunction "1_1") (pintype "passive"))
      (node (ref "J3") (pin "1") (pinfunction "1_1") (pintype "passive"))
      (node (ref "J4") (pin "1") (pinfunction "1_1") (pintype "passive"))
      (node (ref "J4") (pin "2") (pinfunction "2_2") (pintype "passive"))
      (node (ref "J8") (pin "2") (pinfunction "2_2") (pintype "passive"))
      (node (ref "P1") (pin "1") (pinfunction "1_1") (pintype "passive"))
      (node (ref "P10") (pin "1") (pinfunction "1_1") (pintype "passive"))
      (node (ref "P11") (pin "1") (pinfunction "1_1") (pintype "passive"))
      (node (ref "P12") (pin "1") (pinfunction "1_1") (pintype "passive"))
      (node (ref "P14") (pin "1") (pinfunction "1_1") (pintype "passive"))
      (node (ref "P15") (pin "1") (pinfunction "1_1") (pintype "passive"))
      (node (ref "P16") (pin "1") (pinfunction "1_1") (pintype "passive"))
      (node (ref "P17") (pin "1") (pinfunction "1_1") (pintype "passive"))
      (node (ref "P18") (pin "1") (pinfunction "1_1") (pintype "passive"))
      (node (ref "P19") (pin "1") (pinfunction "1_1") (pintype "passive"))
      (node (ref "P2") (pin "1") (pinfunction "1_1") (pintype "passive"))
      (node (ref "P20") (pin "1") (pinfunction "1_1") (pintype "passive"))
      (node (ref "P22") (pin "1") (pinfunction "1_1") (pintype "passive"))
      (node (ref "P23") (pin "1") (pinfunction "1_1") (pintype "passive"))
      (node (ref "P24") (pin "1") (pinfunction "1_1") (pintype "passive"))
      (node (ref "P25") (pin "1") (pinfunction "1_1") (pintype "passive"))
      (node (ref "P26") (pin "1") (pinfunction "1_1") (pintype "passive"))
      (node (ref "P27") (pin "1") (pinfunction "1_1") (pintype "passive"))
      (node (ref "P28") (pin "1") (pinfunction "1_1") (pintype "passive"))
      (node (ref "P3") (pin "1") (pinfunction "1_1") (pintype "passive"))
      (node (ref "P30") (pin "1") (pinfunction "1_1") (pintype "passive"))
      (node (ref "P31") (pin "1") (pinfunction "1_1") (pintype "passive"))
      (node (ref "P32") (pin "1") (pinfunction "1_1") (pintype "passive"))
      (node (ref "P33") (pin "1") (pinfunction "1_1") (pintype "passive"))
      (node (ref "P34") (pin "1") (pinfunction "1_1") (pintype "passive"))
      (node (ref "P35") (pin "1") (pinfunction "1_1") (pintype "passive"))
      (node (ref "P36") (pin "1") (pinfunction "1_1") (pintype "passive"))
      (node (ref "P4") (pin "1") (pinfunction "1_1") (pintype "passive"))
      (node (ref "P6") (pin "1") (pinfunction "1_1") (pintype "passive"))
      (node (ref "P7") (pin "1") (pinfunction "1_1") (pintype "passive"))
      (node (ref "P8") (pin "1") (pinfunction "1_1") (pintype "passive"))
      (node (ref "P9") (pin "1") (pinfunction "1_1") (pintype "passive"))
      (node (ref "U1") (pin "10") (pinfunction "COM_10") (pintype "power_in"))
      (node (ref "U11") (pin "3") (pinfunction "INPUT_3") (pintype "power_in"))
      (node (ref "U3") (pin "10") (pinfunction "COM_10") (pintype "power_in"))
      (node (ref "U4") (pin "10") (pinfunction "COM_10") (pintype "power_in"))
      (node (ref "U7") (pin "10") (pinfunction "COM_10") (pintype "power_in"))
      (node (ref "U9") (pin "10") (pinfunction "COM_10") (pintype "power_in"))
    )
    (net (code "3") (name "/I2C_SCL") (class "Default")
      (node (ref "J2") (pin "3") (pinfunction "3_3") (pintype "passive"))
      (node (ref "J3") (pin "3") (pinfunction "3_3") (pintype "passive"))
      (node (ref "R12") (pin "1") (pinfunction "1_1") (pintype "passive"))
      (node (ref "U10") (pin "26") (pinfunction "SCL_26") (pintype "input"))
      (node (ref "U2") (pin "26") (pinfunction "SCL_26") (pintype "input"))
      (node (ref "U5") (pin "21") (pinfunction "PB10_21") (pintype "bidirectional"))
      (node (ref "U6") (pin "26") (pinfunction "SCL_26") (pintype "input"))
      (node (ref "U8") (pin "8") (pinfunction "SCL_8") (pintype "input"))
    )
    (net (code "4") (name "/I2C_SDA") (class "Default")
      (node (ref "J2") (pin "4") (pinfunction "4_4") (pintype "passive"))
      (node (ref "J3") (pin "4") (pinfunction "4_4") (pintype "passive"))
      (node (ref "R11") (pin "1") (pinfunction "1_1") (pintype "passive"))
      (node (ref "U10") (pin "27") (pinfunction "SDA_27") (pintype "bidirectional"))
      (node (ref "U2") (pin "27") (pinfunction "SDA_27") (pintype "bidirectional"))
      (node (ref "U5") (pin "22") (pinfunction "PB11_22") (pintype "bidirectional"))
      (node (ref "U6") (pin "27") (pinfunction "SDA_27") (pintype "bidirectional"))
      (node (ref "U8") (pin "7") (pinfunction "SDA_7") (pintype "bidirectional"))
    )
    (net (code "5") (name "GND") (class "Default")
      (node (ref "BT1") (pin "2") (pinfunction "-_2") (pintype "passive"))
      (node (ref "C1") (pin "1") (pinfunction "1_1") (pintype "passive"))
      (node (ref "C10") (pin "1") (pinfunction "1_1") (pintype "passive"))
      (node (ref "C11") (pin "1") (pinfunction "1_1") (pintype "passive"))
      (node (ref "C12") (pin "1") (pinfunction "1_1") (pintype "passive"))
      (node (ref "C13") (pin "1") (pinfunction "1_1") (pintype "passive"))
      (node (ref "C14") (pin "1") (pinfunction "1_1") (pintype "passive"))
      (node (ref "C15") (pin "1") (pinfunction "1_1") (pintype "passive"))
      (node (ref "C16") (pin "1") (pinfunction "1_1") (pintype "passive"))
      (node (ref "C17") (pin "1") (pinfunction "1_1") (pintype "passive"))
      (node (ref "C18") (pin "1") (pinfunction "1_1") (pintype "passive"))
      (node (ref "C19") (pin "1") (pinfunction "1_1") (pintype "passive"))
      (node (ref "C2") (pin "1") (pinfunction "1_1") (pintype "passive"))
      (node (ref "C3") (pin "1") (pinfunction "1_1") (pintype "passive"))
      (node (ref "C4") (pin "1") (pinfunction "1_1") (pintype "passive"))
      (node (ref "C5") (pin "1") (pinfunction "1_1") (pintype "passive"))
      (node (ref "C6") (pin "1") (pinfunction "1_1") (pintype "passive"))
      (node (ref "C7") (pin "1") (pinfunction "1_1") (pintype "passive"))
      (node (ref "C8") (pin "1") (pinfunction "1_1") (pintype "passive"))
      (node (ref "C9") (pin "1") (pinfunction "1_1") (pintype "passive"))
      (node (ref "J1") (pin "4") (pinfunction "4_4") (pintype "passive"))
      (node (ref "J1") (pin "5") (pinfunction "5_5") (pintype "passive"))
      (node (ref "J2") (pin "5") (pinfunction "5_5") (pintype "passive"))
      (node (ref "J3") (pin "5") (pinfunction "5_5") (pintype "passive"))
      (node (ref "J4") (pin "4") (pinfunction "4_4") (pintype "passive"))
      (node (ref "J4") (pin "5") (pinfunction "5_5") (pintype "passive"))
      (node (ref "J6") (pin "1") (pinfunction "1_1") (pintype "passive"))
      (node (ref "J7") (pin "5") (pinfunction "GND_5") (pintype "passive"))
      (node (ref "J8") (pin "1") (pinfunction "1_1") (pintype "passive"))
      (node (ref "R18") (pin "1") (pinfunction "1_1") (pintype "passive"))
      (node (ref "R19") (pin "1") (pinfunction "1_1") (pintype "passive"))
      (node (ref "R20") (pin "1") (pinfunction "1_1") (pintype "passive"))
      (node (ref "R21") (pin "1") (pinfunction "1_1") (pintype "passive"))
      (node (ref "R28") (pin "1") (pinfunction "1_1") (pintype "passive"))
      (node (ref "R29") (pin "1") (pinfunction "1_1") (pintype "passive"))
      (node (ref "R30") (pin "1") (pinfunction "1_1") (pintype "passive"))
      (node (ref "R31") (pin "1") (pinfunction "1_1") (pintype "passive"))
      (node (ref "R5") (pin "1") (pinfunction "1_1") (pintype "passive"))
      (node (ref "R6") (pin "1") (pinfunction "1_1") (pintype "passive"))
      (node (ref "R7") (pin "1") (pinfunction "1_1") (pintype "passive"))
      (node (ref "R8") (pin "1") (pinfunction "1_1") (pintype "passive"))
      (node (ref "U1") (pin "9") (pinfunction "GND_9") (pintype "power_in"))
      (node (ref "U10") (pin "14") (pinfunction "VSS_14") (pintype "power_in"))
      (node (ref "U10") (pin "23") (pinfunction "~{OE}_23") (pintype "input"))
      (node (ref "U10") (pin "24") (pinfunction "A5_24") (pintype "input"))
      (node (ref "U10") (pin "25") (pinfunction "EXTCLK_25") (pintype "input"))
      (node (ref "U10") (pin "5") (pinfunction "A4_5") (pintype "input"))
      (node (ref "U11") (pin "1") (pinfunction "GND_1") (pintype "power_in"))
      (node (ref "U2") (pin "14") (pinfunction "VSS_14") (pintype "power_in"))
      (node (ref "U2") (pin "23") (pinfunction "~{OE}_23") (pintype "input"))
      (node (ref "U2") (pin "24") (pinfunction "A5_24") (pintype "input"))
      (node (ref "U2") (pin "25") (pinfunction "EXTCLK_25") (pintype "input"))
      (node (ref "U2") (pin "5") (pinfunction "A4_5") (pintype "input"))
      (node (ref "U3") (pin "9") (pinfunction "GND_9") (pintype "power_in"))
      (node (ref "U4") (pin "9") (pinfunction "GND_9") (pintype "power_in"))
      (node (ref "U5") (pin "23") (pinfunction "VSS_23") (pintype "power_in"))
      (node (ref "U5") (pin "44") (pinfunction "BOOT0_44") (pintype "input"))
      (node (ref "U5") (pin "47") (pinfunction "VSS_47") (pintype "power_in"))
      (node (ref "U5") (pin "8") (pinfunction "VSSA_8") (pintype "power_in"))
      (node (ref "U6") (pin "14") (pinfunction "VSS_14") (pintype "power_in"))
      (node (ref "U6") (pin "23") (pinfunction "~{OE}_23") (pintype "input"))
      (node (ref "U6") (pin "24") (pinfunction "A5_24") (pintype "input"))
      (node (ref "U6") (pin "25") (pinfunction "EXTCLK_25") (pintype "input"))
      (node (ref "U6") (pin "5") (pinfunction "A4_5") (pintype "input"))
      (node (ref "U7") (pin "9") (pinfunction "GND_9") (pintype "power_in"))
      (node (ref "U8") (pin "5") (pinfunction "GND_5") (pintype "power_in"))
      (node (ref "U9") (pin "9") (pinfunction "GND_9") (pintype "power_in"))
    )
    (net (code "6") (name "Net-(BT1-+)") (class "Default")
      (node (ref "BT1") (pin "1") (pinfunction "+_1") (pintype "passive"))
      (node (ref "U8") (pin "6") (pinfunction "VBAT_6") (pintype "power_in"))
    )
    (net (code "7") (name "Net-(D1-C)") (class "Default")
      (node (ref "D1") (pin "1") (pinfunction "C_1") (pintype "passive"))
      (node (ref "R9") (pin "2") (pinfunction "2_2") (pintype "passive"))
    )
    (net (code "8") (name "Net-(D2-C)") (class "Default")
      (node (ref "D2") (pin "1") (pinfunction "C_1") (pintype "passive"))
      (node (ref "R10") (pin "2") (pinfunction "2_2") (pintype "passive"))
    )
    (net (code "9") (name "Net-(J7-NRESET)") (class "Default")
      (node (ref "J7") (pin "3") (pinfunction "NRESET_3") (pintype "passive"))
      (node (ref "R13") (pin "1") (pinfunction "1_1") (pintype "passive"))
      (node (ref "U5") (pin "7") (pinfunction "NRST_7") (pintype "bidirectional"))
    )
    (net (code "10") (name "Net-(J7-SWCLK)") (class "Default")
      (node (ref "J7") (pin "4") (pinfunction "SWCLK_4") (pintype "passive"))
      (node (ref "U5") (pin "37") (pinfunction "PA14(SWCLK)_37") (pintype "bidirectional"))
    )
    (net (code "11") (name "Net-(J7-SWDIO)") (class "Default")
      (node (ref "J7") (pin "2") (pinfunction "SWDIO_2") (pintype "passive"))
      (node (ref "U5") (pin "34") (pinfunction "PA13(SWDIO)_34") (pintype "bidirectional"))
    )
    (net (code "12") (name "Net-(U1-1B)") (class "Default")
      (node (ref "U1") (pin "1") (pinfunction "1B_1") (pintype "input"))
      (node (ref "U2") (pin "6") (pinfunction "LED0_6") (pintype "passive"))
    )
    (net (code "13") (name "Net-(U1-1C)") (class "Default")
      (node (ref "P1") (pin "2") (pinfunction "2_2") (pintype "passive"))
      (node (ref "U1") (pin "18") (pinfunction "1C_18") (pintype "output"))
    )
    (net (code "14") (name "Net-(U1-2B)") (class "Default")
      (node (ref "U1") (pin "2") (pinfunction "2B_2") (pintype "input"))
      (node (ref "U2") (pin "7") (pinfunction "LED1_7") (pintype "passive"))
    )
    (net (code "15") (name "Net-(U1-2C)") (class "Default")
      (node (ref "P2") (pin "2") (pinfunction "2_2") (pintype "passive"))
      (node (ref "U1") (pin "17") (pinfunction "2C_17") (pintype "output"))
    )
    (net (code "16") (name "Net-(U1-3B)") (class "Default")
      (node (ref "U1") (pin "3") (pinfunction "3B_3") (pintype "input"))
      (node (ref "U2") (pin "8") (pinfunction "LED2_8") (pintype "passive"))
    )
    (net (code "17") (name "Net-(U1-3C)") (class "Default")
      (node (ref "P3") (pin "2") (pinfunction "2_2") (pintype "passive"))
      (node (ref "U1") (pin "16") (pinfunction "3C_16") (pintype "output"))
    )
    (net (code "18") (name "Net-(U1-4B)") (class "Default")
      (node (ref "U1") (pin "4") (pinfunction "4B_4") (pintype "input"))
      (node (ref "U2") (pin "9") (pinfunction "LED3_9") (pintype "passive"))
    )
    (net (code "19") (name "Net-(U1-4C)") (class "Default")
      (node (ref "P4") (pin "2") (pinfunction "2_2") (pintype "passive"))
      (node (ref "U1") (pin "15") (pinfunction "4C_15") (pintype "output"))
    )
    (net (code "20") (name "Net-(U1-5B)") (class "Default")
      (node (ref "U1") (pin "5") (pinfunction "5B_5") (pintype "input"))
      (node (ref "U2") (pin "10") (pinfunction "LED4_10") (pintype "passive"))
    )
    (net (code "21") (name "Net-(U1-5C)") (class "Default")
      (node (ref "P5") (pin "2") (pinfunction "2_2") (pintype "passive"))
      (node (ref "U1") (pin "14") (pinfunction "5C_14") (pintype "output"))
    )
    (net (code "22") (name "Net-(U1-6B)") (class "Default")
      (node (ref "U1") (pin "6") (pinfunction "6B_6") (pintype "input"))
      (node (ref "U2") (pin "11") (pinfunction "LED5_11") (pintype "passive"))
    )
    (net (code "23") (name "Net-(U1-6C)") (class "Default")
      (node (ref "P6") (pin "2") (pinfunction "2_2") (pintype "passive"))
      (node (ref "U1") (pin "13") (pinfunction "6C_13") (pintype "output"))
    )
    (net (code "24") (name "Net-(U1-7B)") (class "Default")
      (node (ref "U1") (pin "7") (pinfunction "7B_7") (pintype "input"))
      (node (ref "U2") (pin "12") (pinfunction "LED6_12") (pintype "passive"))
    )
    (net (code "25") (name "Net-(U1-7C)") (class "Default")
      (node (ref "P7") (pin "2") (pinfunction "2_2") (pintype "passive"))
      (node (ref "U1") (pin "12") (pinfunction "7C_12") (pintype "output"))
    )
    (net (code "26") (name "Net-(U1-8B)") (class "Default")
      (node (ref "U1") (pin "8") (pinfunction "8B_8") (pintype "input"))
      (node (ref "U2") (pin "13") (pinfunction "LED7_13") (pintype "passive"))
    )
    (net (code "27") (name "Net-(U1-8C)") (class "Default")
      (node (ref "P8") (pin "2") (pinfunction "2_2") (pintype "passive"))
      (node (ref "U1") (pin "11") (pinfunction "8C_11") (pintype "output"))
    )
    (net (code "28") (name "Net-(U2-A0)") (class "Default")
      (node (ref "R4") (pin "1") (pinfunction "1_1") (pintype "passive"))
      (node (ref "R8") (pin "2") (pinfunction "2_2") (pintype "passive"))
      (node (ref "U2") (pin "1") (pinfunction "A0_1") (pintype "input"))
    )
    (net (code "29") (name "Net-(U2-A1)") (class "Default")
      (node (ref "R3") (pin "1") (pinfunction "1_1") (pintype "passive"))
      (node (ref "R7") (pin "2") (pinfunction "2_2") (pintype "passive"))
      (node (ref "U2") (pin "2") (pinfunction "A1_2") (pintype "input"))
    )
    (net (code "30") (name "Net-(U2-A2)") (class "Default")
      (node (ref "R2") (pin "1") (pinfunction "1_1") (pintype "passive"))
      (node (ref "R6") (pin "2") (pinfunction "2_2") (pintype "passive"))
      (node (ref "U2") (pin "3") (pinfunction "A2_3") (pintype "input"))
    )
    (net (code "31") (name "Net-(U2-A3)") (class "Default")
      (node (ref "R1") (pin "1") (pinfunction "1_1") (pintype "passive"))
      (node (ref "R5") (pin "2") (pinfunction "2_2") (pintype "passive"))
      (node (ref "U2") (pin "4") (pinfunction "A3_4") (pintype "input"))
    )
    (net (code "32") (name "Net-(U2-LED8)") (class "Default")
      (node (ref "U2") (pin "15") (pinfunction "LED8_15") (pintype "passive"))
      (node (ref "U3") (pin "1") (pinfunction "1B_1") (pintype "input"))
    )
    (net (code "33") (name "Net-(U2-LED9)") (class "Default")
      (node (ref "U2") (pin "16") (pinfunction "LED9_16") (pintype "passive"))
      (node (ref "U3") (pin "2") (pinfunction "2B_2") (pintype "input"))
    )
    (net (code "34") (name "Net-(U2-LED10)") (class "Default")
      (node (ref "U2") (pin "17") (pinfunction "LED10_17") (pintype "passive"))
      (node (ref "U3") (pin "3") (pinfunction "3B_3") (pintype "input"))
    )
    (net (code "35") (name "Net-(U2-LED11)") (class "Default")
      (node (ref "U2") (pin "18") (pinfunction "LED11_18") (pintype "passive"))
      (node (ref "U3") (pin "4") (pinfunction "4B_4") (pintype "input"))
    )
    (net (code "36") (name "Net-(U2-LED12)") (class "Default")
      (node (ref "U2") (pin "19") (pinfunction "LED12_19") (pintype "passive"))
      (node (ref "U3") (pin "5") (pinfunction "5B_5") (pintype "input"))
    )
    (net (code "37") (name "Net-(U2-LED13)") (class "Default")
      (node (ref "U2") (pin "20") (pinfunction "LED13_20") (pintype "passive"))
      (node (ref "U3") (pin "6") (pinfunction "6B_6") (pintype "input"))
    )
    (net (code "38") (name "Net-(U2-LED14)") (class "Default")
      (node (ref "U2") (pin "21") (pinfunction "LED14_21") (pintype "passive"))
      (node (ref "U3") (pin "7") (pinfunction "7B_7") (pintype "input"))
    )
    (net (code "39") (name "Net-(U2-LED15)") (class "Default")
      (node (ref "U2") (pin "22") (pinfunction "LED15_22") (pintype "passive"))
      (node (ref "U3") (pin "8") (pinfunction "8B_8") (pintype "input"))
    )
    (net (code "40") (name "Net-(U3-1C)") (class "Default")
      (node (ref "P9") (pin "2") (pinfunction "2_2") (pintype "passive"))
      (node (ref "U3") (pin "18") (pinfunction "1C_18") (pintype "output"))
    )
    (net (code "41") (name "Net-(U3-2C)") (class "Default")
      (node (ref "P10") (pin "2") (pinfunction "2_2") (pintype "passive"))
      (node (ref "U3") (pin "17") (pinfunction "2C_17") (pintype "output"))
    )
    (net (code "42") (name "Net-(U3-3C)") (class "Default")
      (node (ref "P11") (pin "2") (pinfunction "2_2") (pintype "passive"))
      (node (ref "U3") (pin "16") (pinfunction "3C_16") (pintype "output"))
    )
    (net (code "43") (name "Net-(U3-4C)") (class "Default")
      (node (ref "P12") (pin "2") (pinfunction "2_2") (pintype "passive"))
      (node (ref "U3") (pin "15") (pinfunction "4C_15") (pintype "output"))
    )
    (net (code "44") (name "Net-(U3-5C)") (class "Default")
      (node (ref "P13") (pin "2") (pinfunction "2_2") (pintype "passive"))
      (node (ref "U3") (pin "14") (pinfunction "5C_14") (pintype "output"))
    )
    (net (code "45") (name "Net-(U3-6C)") (class "Default")
      (node (ref "P14") (pin "2") (pinfunction "2_2") (pintype "passive"))
      (node (ref "U3") (pin "13") (pinfunction "6C_13") (pintype "output"))
    )
    (net (code "46") (name "Net-(U3-7C)") (class "Default")
      (node (ref "P15") (pin "2") (pinfunction "2_2") (pintype "passive"))
      (node (ref "U3") (pin "12") (pinfunction "7C_12") (pintype "output"))
    )
    (net (code "47") (name "Net-(U3-8C)") (class "Default")
      (node (ref "P16") (pin "2") (pinfunction "2_2") (pintype "passive"))
      (node (ref "U3") (pin "11") (pinfunction "8C_11") (pintype "output"))
    )
    (net (code "48") (name "Net-(U4-1B)") (class "Default")
      (node (ref "U4") (pin "1") (pinfunction "1B_1") (pintype "input"))
      (node (ref "U6") (pin "6") (pinfunction "LED0_6") (pintype "passive"))
    )
    (net (code "49") (name "Net-(U4-1C)") (class "Default")
      (node (ref "P17") (pin "2") (pinfunction "2_2") (pintype "passive"))
      (node (ref "U4") (pin "18") (pinfunction "1C_18") (pintype "output"))
    )
    (net (code "50") (name "Net-(U4-2B)") (class "Default")
      (node (ref "U4") (pin "2") (pinfunction "2B_2") (pintype "input"))
      (node (ref "U6") (pin "7") (pinfunction "LED1_7") (pintype "passive"))
    )
    (net (code "51") (name "Net-(U4-2C)") (class "Default")
      (node (ref "P18") (pin "2") (pinfunction "2_2") (pintype "passive"))
      (node (ref "U4") (pin "17") (pinfunction "2C_17") (pintype "output"))
    )
    (net (code "52") (name "Net-(U4-3B)") (class "Default")
      (node (ref "U4") (pin "3") (pinfunction "3B_3") (pintype "input"))
      (node (ref "U6") (pin "8") (pinfunction "LED2_8") (pintype "passive"))
    )
    (net (code "53") (name "Net-(U4-3C)") (class "Default")
      (node (ref "P19") (pin "2") (pinfunction "2_2") (pintype "passive"))
      (node (ref "U4") (pin "16") (pinfunction "3C_16") (pintype "output"))
    )
    (net (code "54") (name "Net-(U4-4B)") (class "Default")
      (node (ref "U4") (pin "4") (pinfunction "4B_4") (pintype "input"))
      (node (ref "U6") (pin "9") (pinfunction "LED3_9") (pintype "passive"))
    )
    (net (code "55") (name "Net-(U4-4C)") (class "Default")
      (node (ref "P20") (pin "2") (pinfunction "2_2") (pintype "passive"))
      (node (ref "U4") (pin "15") (pinfunction "4C_15") (pintype "output"))
    )
    (net (code "56") (name "Net-(U4-5B)") (class "Default")
      (node (ref "U4") (pin "5") (pinfunction "5B_5") (pintype "input"))
      (node (ref "U6") (pin "10") (pinfunction "LED4_10") (pintype "passive"))
    )
    (net (code "57") (name "Net-(U4-5C)") (class "Default")
      (node (ref "P21") (pin "2") (pinfunction "2_2") (pintype "passive"))
      (node (ref "U4") (pin "14") (pinfunction "5C_14") (pintype "output"))
    )
    (net (code "58") (name "Net-(U4-6B)") (class "Default")
      (node (ref "U4") (pin "6") (pinfunction "6B_6") (pintype "input"))
      (node (ref "U6") (pin "11") (pinfunction "LED5_11") (pintype "passive"))
    )
    (net (code "59") (name "Net-(U4-6C)") (class "Default")
      (node (ref "P22") (pin "2") (pinfunction "2_2") (pintype "passive"))
      (node (ref "U4") (pin "13") (pinfunction "6C_13") (pintype "output"))
    )
    (net (code "60") (name "Net-(U4-7B)") (class "Default")
      (node (ref "U4") (pin "7") (pinfunction "7B_7") (pintype "input"))
      (node (ref "U6") (pin "12") (pinfunction "LED6_12") (pintype "passive"))
    )
    (net (code "61") (name "Net-(U4-7C)") (class "Default")
      (node (ref "P23") (pin "2") (pinfunction "2_2") (pintype "passive"))
      (node (ref "U4") (pin "12") (pinfunction "7C_12") (pintype "output"))
    )
    (net (code "62") (name "Net-(U4-8B)") (class "Default")
      (node (ref "U4") (pin "8") (pinfunction "8B_8") (pintype "input"))
      (node (ref "U6") (pin "13") (pinfunction "LED7_13") (pintype "passive"))
    )
    (net (code "63") (name "Net-(U4-8C)") (class "Default")
      (node (ref "P24") (pin "2") (pinfunction "2_2") (pintype "passive"))
      (node (ref "U4") (pin "11") (pinfunction "8C_11") (pintype "output"))
    )
    (net (code "64") (name "Net-(U5-PA0)") (class "Default")
      (node (ref "R10") (pin "1") (pinfunction "1_1") (pintype "passive"))
      (node (ref "U5") (pin "10") (pinfunction "PA0_10") (pintype "bidirectional"))
    )
    (net (code "65") (name "Net-(U5-PA1)") (class "Default")
      (node (ref "R9") (pin "1") (pinfunction "1_1") (pintype "passive"))
      (node (ref "U5") (pin "11") (pinfunction "PA1_11") (pintype "bidirectional"))
    )
    (net (code "66") (name "Net-(U5-PA3)") (class "Default")
      (node (ref "J5") (pin "2") (pinfunction "2_2") (pintype "passive"))
      (node (ref "U5") (pin "13") (pinfunction "PA3_13") (pintype "bidirectional"))
    )
    (net (code "67") (name "Net-(U5-PA4)") (class "Default")
      (node (ref "J5") (pin "3") (pinfunction "3_3") (pintype "passive"))
      (node (ref "U5") (pin "14") (pinfunction "PA4_14") (pintype "bidirectional"))
    )
    (net (code "68") (name "Net-(U5-PA5)") (class "Default")
      (node (ref "J5") (pin "4") (pinfunction "4_4") (pintype "passive"))
      (node (ref "U5") (pin "15") (pinfunction "PA5_15") (pintype "bidirectional"))
    )
    (net (code "69") (name "Net-(U5-PA6)") (class "Default")
      (node (ref "J5") (pin "5") (pinfunction "5_5") (pintype "passive"))
      (node (ref "U5") (pin "16") (pinfunction "PA6_16") (pintype "bidirectional"))
    )
    (net (code "70") (name "Net-(U5-PA15)") (class "Default")
      (node (ref "R23") (pin "1") (pinfunction "1_1") (pintype "passive"))
      (node (ref "U5") (pin "38") (pinfunction "PA15_38") (pintype "bidirectional"))
      (node (ref "U8") (pin "3") (pinfunction "~{INT}/SQW_3") (pintype "bidirectional"))
    )
    (net (code "71") (name "Net-(U5-PB3)") (class "Default")
      (node (ref "R22") (pin "1") (pinfunction "1_1") (pintype "passive"))
      (node (ref "U5") (pin "39") (pinfunction "PB3_39") (pintype "bidirectional"))
      (node (ref "U8") (pin "1") (pinfunction "32kHz_1") (pintype "open_collector"))
    )
    (net (code "72") (name "Net-(U5-PB4)") (class "Default")
      (node (ref "J6") (pin "5") (pinfunction "5_5") (pintype "passive"))
      (node (ref "U5") (pin "40") (pinfunction "PB4_40") (pintype "bidirectional"))
    )
    (net (code "73") (name "Net-(U5-PB5)") (class "Default")
      (node (ref "J6") (pin "4") (pinfunction "4_4") (pintype "passive"))
      (node (ref "U5") (pin "41") (pinfunction "PB5_41") (pintype "bidirectional"))
    )
    (net (code "74") (name "Net-(U5-PB6)") (class "Default")
      (node (ref "J6") (pin "3") (pinfunction "3_3") (pintype "passive"))
      (node (ref "U5") (pin "42") (pinfunction "PB6_42") (pintype "bidirectional"))
    )
    (net (code "75") (name "Net-(U5-PB7)") (class "Default")
      (node (ref "J6") (pin "2") (pinfunction "2_2") (pintype "passive"))
      (node (ref "U5") (pin "43") (pinfunction "PB7_43") (pintype "bidirectional"))
    )
    (net (code "76") (name "Net-(U5-PC13)") (class "Default")
      (node (ref "SW1") (pin "1") (pinfunction "1_1") (pintype "passive"))
      (node (ref "SW1") (pin "3") (pinfunction "3_3") (pintype "passive"))
      (node (ref "U5") (pin "2") (pinfunction "PC13_2") (pintype "bidirectional"))
    )
    (net (code "77") (name "Net-(U6-A0)") (class "Default")
      (node (ref "R17") (pin "1") (pinfunction "1_1") (pintype "passive"))
      (node (ref "R21") (pin "2") (pinfunction "2_2") (pintype "passive"))
      (node (ref "U6") (pin "1") (pinfunction "A0_1") (pintype "input"))
    )
    (net (code "78") (name "Net-(U6-A1)") (class "Default")
      (node (ref "R16") (pin "1") (pinfunction "1_1") (pintype "passive"))
      (node (ref "R20") (pin "2") (pinfunction "2_2") (pintype "passive"))
      (node (ref "U6") (pin "2") (pinfunction "A1_2") (pintype "input"))
    )
    (net (code "79") (name "Net-(U6-A2)") (class "Default")
      (node (ref "R15") (pin "1") (pinfunction "1_1") (pintype "passive"))
      (node (ref "R19") (pin "2") (pinfunction "2_2") (pintype "passive"))
      (node (ref "U6") (pin "3") (pinfunction "A2_3") (pintype "input"))
    )
    (net (code "80") (name "Net-(U6-A3)") (class "Default")
      (node (ref "R14") (pin "1") (pinfunction "1_1") (pintype "passive"))
      (node (ref "R18") (pin "2") (pinfunction "2_2") (pintype "passive"))
      (node (ref "U6") (pin "4") (pinfunction "A3_4") (pintype "input"))
    )
    (net (code "81") (name "Net-(U6-LED8)") (class "Default")
      (node (ref "U6") (pin "15") (pinfunction "LED8_15") (pintype "passive"))
      (node (ref "U7") (pin "1") (pinfunction "1B_1") (pintype "input"))
    )
    (net (code "82") (name "Net-(U6-LED9)") (class "Default")
      (node (ref "U6") (pin "16") (pinfunction "LED9_16") (pintype "passive"))
      (node (ref "U7") (pin "2") (pinfunction "2B_2") (pintype "input"))
    )
    (net (code "83") (name "Net-(U6-LED10)") (class "Default")
      (node (ref "U6") (pin "17") (pinfunction "LED10_17") (pintype "passive"))
      (node (ref "U7") (pin "3") (pinfunction "3B_3") (pintype "input"))
    )
    (net (code "84") (name "Net-(U6-LED11)") (class "Default")
      (node (ref "U6") (pin "18") (pinfunction "LED11_18") (pintype "passive"))
      (node (ref "U7") (pin "4") (pinfunction "4B_4") (pintype "input"))
    )
    (net (code "85") (name "Net-(U6-LED12)") (class "Default")
      (node (ref "U6") (pin "19") (pinfunction "LED12_19") (pintype "passive"))
      (node (ref "U7") (pin "5") (pinfunction "5B_5") (pintype "input"))
    )
    (net (code "86") (name "Net-(U6-LED13)") (class "Default")
      (node (ref "U6") (pin "20") (pinfunction "LED13_20") (pintype "passive"))
      (node (ref "U7") (pin "6") (pinfunction "6B_6") (pintype "input"))
    )
    (net (code "87") (name "Net-(U6-LED14)") (class "Default")
      (node (ref "U6") (pin "21") (pinfunction "LED14_21") (pintype "passive"))
      (node (ref "U7") (pin "7") (pinfunction "7B_7") (pintype "input"))
    )
    (net (code "88") (name "Net-(U6-LED15)") (class "Default")
      (node (ref "U6") (pin "22") (pinfunction "LED15_22") (pintype "passive"))
      (node (ref "U7") (pin "8") (pinfunction "8B_8") (pintype "input"))
    )
    (net (code "89") (name "Net-(U7-1C)") (class "Default")
      (node (ref "P25") (pin "2") (pinfunction "2_2") (pintype "passive"))
      (node (ref "U7") (pin "18") (pinfunction "1C_18") (pintype "output"))
    )
    (net (code "90") (name "Net-(U7-2C)") (class "Default")
      (node (ref "P26") (pin "2") (pinfunction "2_2") (pintype "passive"))
      (node (ref "U7") (pin "17") (pinfunction "2C_17") (pintype "output"))
    )
    (net (code "91") (name "Net-(U7-3C)") (class "Default")
      (node (ref "P27") (pin "2") (pinfunction "2_2") (pintype "passive"))
      (node (ref "U7") (pin "16") (pinfunction "3C_16") (pintype "output"))
    )
    (net (code "92") (name "Net-(U7-4C)") (class "Default")
      (node (ref "P28") (pin "2") (pinfunction "2_2") (pintype "passive"))
      (node (ref "U7") (pin "15") (pinfunction "4C_15") (pintype "output"))
    )
    (net (code "93") (name "Net-(U7-5C)") (class "Default")
      (node (ref "P29") (pin "2") (pinfunction "2_2") (pintype "passive"))
      (node (ref "U7") (pin "14") (pinfunction "5C_14") (pintype "output"))
    )
    (net (code "94") (name "Net-(U7-6C)") (class "Default")
      (node (ref "P30") (pin "2") (pinfunction "2_2") (pintype "passive"))
      (node (ref "U7") (pin "13") (pinfunction "6C_13") (pintype "output"))
    )
    (net (code "95") (name "Net-(U7-7C)") (class "Default")
      (node (ref "P31") (pin "2") (pinfunction "2_2") (pintype "passive"))
      (node (ref "U7") (pin "12") (pinfunction "7C_12") (pintype "output"))
    )
    (net (code "96") (name "Net-(U7-8C)") (class "Default")
      (node (ref "P32") (pin "2") (pinfunction "2_2") (pintype "passive"))
      (node (ref "U7") (pin "11") (pinfunction "8C_11") (pintype "output"))
    )
    (net (code "97") (name "Net-(U9-1C)") (class "Default")
      (node (ref "P33") (pin "2") (pinfunction "2_2") (pintype "passive"))
      (node (ref "U9") (pin "18") (pinfunction "1C_18") (pintype "output"))
    )
    (net (code "98") (name "Net-(U9-2C)") (class "Default")
      (node (ref "P34") (pin "2") (pinfunction "2_2") (pintype "passive"))
      (node (ref "U9") (pin "17") (pinfunction "2C_17") (pintype "output"))
    )
    (net (code "99") (name "Net-(U9-3C)") (class "Default")
      (node (ref "P35") (pin "2") (pinfunction "2_2") (pintype "passive"))
      (node (ref "U9") (pin "16") (pinfunction "3C_16") (pintype "output"))
    )
    (net (code "100") (name "Net-(U9-4C)") (class "Default")
      (node (ref "P36") (pin "2") (pinfunction "2_2") (pintype "passive"))
      (node (ref "U9") (pin "15") (pinfunction "4C_15") (pintype "output"))
    )
    (net (code "101") (name "Net-(U10-A0)") (class "Default")
      (node (ref "R27") (pin "1") (pinfunction "1_1") (pintype "passive"))
      (node (ref "R31") (pin "2") (pinfunction "2_2") (pintype "passive"))
      (node (ref "U10") (pin "1") (pinfunction "A0_1") (pintype "input"))
    )
    (net (code "102") (name "Net-(U10-A1)") (class "Default")
      (node (ref "R26") (pin "1") (pinfunction "1_1") (pintype "passive"))
      (node (ref "R30") (pin "2") (pinfunction "2_2") (pintype "passive"))
      (node (ref "U10") (pin "2") (pinfunction "A1_2") (pintype "input"))
    )
    (net (code "103") (name "Net-(U10-A2)") (class "Default")
      (node (ref "R25") (pin "1") (pinfunction "1_1") (pintype "passive"))
      (node (ref "R29") (pin "2") (pinfunction "2_2") (pintype "passive"))
      (node (ref "U10") (pin "3") (pinfunction "A2_3") (pintype "input"))
    )
    (net (code "104") (name "Net-(U10-A3)") (class "Default")
      (node (ref "R24") (pin "1") (pinfunction "1_1") (pintype "passive"))
      (node (ref "R28") (pin "2") (pinfunction "2_2") (pintype "passive"))
      (node (ref "U10") (pin "4") (pinfunction "A3_4") (pintype "input"))
    )
    (net (code "105") (name "Net-(U10-LED0)") (class "Default")
      (node (ref "U10") (pin "6") (pinfunction "LED0_6") (pintype "passive"))
      (node (ref "U9") (pin "1") (pinfunction "1B_1") (pintype "input"))
    )
    (net (code "106") (name "Net-(U10-LED1)") (class "Default")
      (node (ref "U10") (pin "7") (pinfunction "LED1_7") (pintype "passive"))
      (node (ref "U9") (pin "2") (pinfunction "2B_2") (pintype "input"))
    )
    (net (code "107") (name "Net-(U10-LED2)") (class "Default")
      (node (ref "U10") (pin "8") (pinfunction "LED2_8") (pintype "passive"))
      (node (ref "U9") (pin "3") (pinfunction "3B_3") (pintype "input"))
    )
    (net (code "108") (name "Net-(U10-LED3)") (class "Default")
      (node (ref "U10") (pin "9") (pinfunction "LED3_9") (pintype "passive"))
      (node (ref "U9") (pin "4") (pinfunction "4B_4") (pintype "input"))
    )
    (net (code "109") (name "Net-(U10-LED4)") (class "Default")
      (node (ref "U10") (pin "10") (pinfunction "LED4_10") (pintype "passive"))
      (node (ref "U9") (pin "5") (pinfunction "5B_5") (pintype "input"))
    )
    (net (code "110") (name "Net-(U10-LED5)") (class "Default")
      (node (ref "U10") (pin "11") (pinfunction "LED5_11") (pintype "passive"))
      (node (ref "U9") (pin "6") (pinfunction "6B_6") (pintype "input"))
    )
    (net (code "111") (name "Net-(U10-LED6)") (class "Default")
      (node (ref "U10") (pin "12") (pinfunction "LED6_12") (pintype "passive"))
      (node (ref "U9") (pin "7") (pinfunction "7B_7") (pintype "input"))
    )
    (net (code "112") (name "Net-(U10-LED7)") (class "Default")
      (node (ref "U10") (pin "13") (pinfunction "LED7_13") (pintype "passive"))
      (node (ref "U9") (pin "8") (pinfunction "8B_8") (pintype "input"))
    )
    (net (code "113") (name "unconnected-(J7-SWO-Pad6)") (class "Default")
      (node (ref "J7") (pin "6") (pinfunction "SWO_6") (pintype "passive"))
    )
    (net (code "114") (name "unconnected-(P5-Pad1)") (class "Default")
      (node (ref "P5") (pin "1") (pinfunction "1_1") (pintype "passive"))
    )
    (net (code "115") (name "unconnected-(P13-Pad1)") (class "Default")
      (node (ref "P13") (pin "1") (pinfunction "1_1") (pintype "passive"))
    )
    (net (code "116") (name "unconnected-(P21-Pad1)") (class "Default")
      (node (ref "P21") (pin "1") (pinfunction "1_1") (pintype "passive"))
    )
    (net (code "117") (name "unconnected-(P29-Pad1)") (class "Default")
      (node (ref "P29") (pin "1") (pinfunction "1_1") (pintype "passive"))
    )
    (net (code "118") (name "unconnected-(U5-PA2-Pad12)") (class "Default")
      (node (ref "U5") (pin "12") (pinfunction "PA2_12") (pintype "bidirectional"))
    )
    (net (code "119") (name "unconnected-(U5-PA7-Pad17)") (class "Default")
      (node (ref "U5") (pin "17") (pinfunction "PA7_17") (pintype "bidirectional"))
    )
    (net (code "120") (name "unconnected-(U5-PA8-Pad29)") (class "Default")
      (node (ref "U5") (pin "29") (pinfunction "PA8_29") (pintype "bidirectional"))
    )
    (net (code "121") (name "unconnected-(U5-PA9-Pad30)") (class "Default")
      (node (ref "U5") (pin "30") (pinfunction "PA9_30") (pintype "bidirectional"))
    )
    (net (code "122") (name "unconnected-(U5-PA10-Pad31)") (class "Default")
      (node (ref "U5") (pin "31") (pinfunction "PA10_31") (pintype "bidirectional"))
    )
    (net (code "123") (name "unconnected-(U5-PA11-Pad32)") (class "Default")
      (node (ref "U5") (pin "32") (pinfunction "PA11_32") (pintype "bidirectional"))
    )
    (net (code "124") (name "unconnected-(U5-PA12-Pad33)") (class "Default")
      (node (ref "U5") (pin "33") (pinfunction "PA12_33") (pintype "bidirectional"))
    )
    (net (code "125") (name "unconnected-(U5-PB0-Pad18)") (class "Default")
      (node (ref "U5") (pin "18") (pinfunction "PB0_18") (pintype "bidirectional"))
    )
    (net (code "126") (name "unconnected-(U5-PB1-Pad19)") (class "Default")
      (node (ref "U5") (pin "19") (pinfunction "PB1_19") (pintype "bidirectional"))
    )
    (net (code "127") (name "unconnected-(U5-PB2-Pad20)") (class "Default")
      (node (ref "U5") (pin "20") (pinfunction "PB2_20") (pintype "bidirectional"))
    )
    (net (code "128") (name "unconnected-(U5-PB8-Pad45)") (class "Default")
      (node (ref "U5") (pin "45") (pinfunction "PB8_45") (pintype "bidirectional"))
    )
    (net (code "129") (name "unconnected-(U5-PB9-Pad46)") (class "Default")
      (node (ref "U5") (pin "46") (pinfunction "PB9_46") (pintype "bidirectional"))
    )
    (net (code "130") (name "unconnected-(U5-PB12-Pad25)") (class "Default")
      (node (ref "U5") (pin "25") (pinfunction "PB12_25") (pintype "bidirectional"))
    )
    (net (code "131") (name "unconnected-(U5-PB13-Pad26)") (class "Default")
      (node (ref "U5") (pin "26") (pinfunction "PB13_26") (pintype "bidirectional"))
    )
    (net (code "132") (name "unconnected-(U5-PB14-Pad27)") (class "Default")
      (node (ref "U5") (pin "27") (pinfunction "PB14_27") (pintype "bidirectional"))
    )
    (net (code "133") (name "unconnected-(U5-PB15-Pad28)") (class "Default")
      (node (ref "U5") (pin "28") (pinfunction "PB15_28") (pintype "bidirectional"))
    )
    (net (code "134") (name "unconnected-(U5-PC14-OSC32_IN(PC14)-Pad3)") (class "Default")
      (node (ref "U5") (pin "3") (pinfunction "PC14-OSC32_IN(PC14)_3") (pintype "bidirectional"))
    )
    (net (code "135") (name "unconnected-(U5-PC15-OSC32_OUT(PC15)-Pad4)") (class "Default")
      (node (ref "U5") (pin "4") (pinfunction "PC15-OSC32_OUT(PC15)_4") (pintype "bidirectional"))
    )
    (net (code "136") (name "unconnected-(U5-PF0-OSC_IN(PF0)-Pad5)") (class "Default")
      (node (ref "U5") (pin "5") (pinfunction "PF0-OSC_IN(PF0)_5") (pintype "bidirectional"))
    )
    (net (code "137") (name "unconnected-(U5-PF1-OSC_OUT(PF1)-Pad6)") (class "Default")
      (node (ref "U5") (pin "6") (pinfunction "PF1-OSC_OUT(PF1)_6") (pintype "bidirectional"))
    )
    (net (code "138") (name "unconnected-(U5-PF6-Pad35)") (class "Default")
      (node (ref "U5") (pin "35") (pinfunction "PF6_35") (pintype "bidirectional"))
    )
    (net (code "139") (name "unconnected-(U5-PF7-Pad36)") (class "Default")
      (node (ref "U5") (pin "36") (pinfunction "PF7_36") (pintype "bidirectional"))
    )
    (net (code "140") (name "unconnected-(U9-5C-Pad14)") (class "Default")
      (node (ref "U9") (pin "14") (pinfunction "5C_14") (pintype "output"))
    )
    (net (code "141") (name "unconnected-(U9-6C-Pad13)") (class "Default")
      (node (ref "U9") (pin "13") (pinfunction "6C_13") (pintype "output"))
    )
    (net (code "142") (name "unconnected-(U9-7C-Pad12)") (class "Default")
      (node (ref "U9") (pin "12") (pinfunction "7C_12") (pintype "output"))
    )
    (net (code "143") (name "unconnected-(U9-8C-Pad11)") (class "Default")
      (node (ref "U9") (pin "11") (pinfunction "8C_11") (pintype "output"))
    )
    (net (code "144") (name "unconnected-(U10-LED8-Pad15)") (class "Default")
      (node (ref "U10") (pin "15") (pinfunction "LED8_15") (pintype "passive"))
    )
    (net (code "145") (name "unconnected-(U10-LED9-Pad16)") (class "Default")
      (node (ref "U10") (pin "16") (pinfunction "LED9_16") (pintype "passive"))
    )
    (net (code "146") (name "unconnected-(U10-LED10-Pad17)") (class "Default")
      (node (ref "U10") (pin "17") (pinfunction "LED10_17") (pintype "passive"))
    )
    (net (code "147") (name "unconnected-(U10-LED11-Pad18)") (class "Default")
      (node (ref "U10") (pin "18") (pinfunction "LED11_18") (pintype "passive"))
    )
    (net (code "148") (name "unconnected-(U10-LED12-Pad19)") (class "Default")
      (node (ref "U10") (pin "19") (pinfunction "LED12_19") (pintype "passive"))
    )
    (net (code "149") (name "unconnected-(U10-LED13-Pad20)") (class "Default")
      (node (ref "U10") (pin "20") (pinfunction "LED13_20") (pintype "passive"))
    )
    (net (code "150") (name "unconnected-(U10-LED14-Pad21)") (class "Default")
      (node (ref "U10") (pin "21") (pinfunction "LED14_21") (pintype "passive"))
    )
    (net (code "151") (name "unconnected-(U10-LED15-Pad22)") (class "Default")
      (node (ref "U10") (pin "22") (pinfunction "LED15_22") (pintype "passive"))
    )
  )
)
